# Sheet_1_2023-03-25.net
KiCad netlist of a schematic drawn in Altium Designer
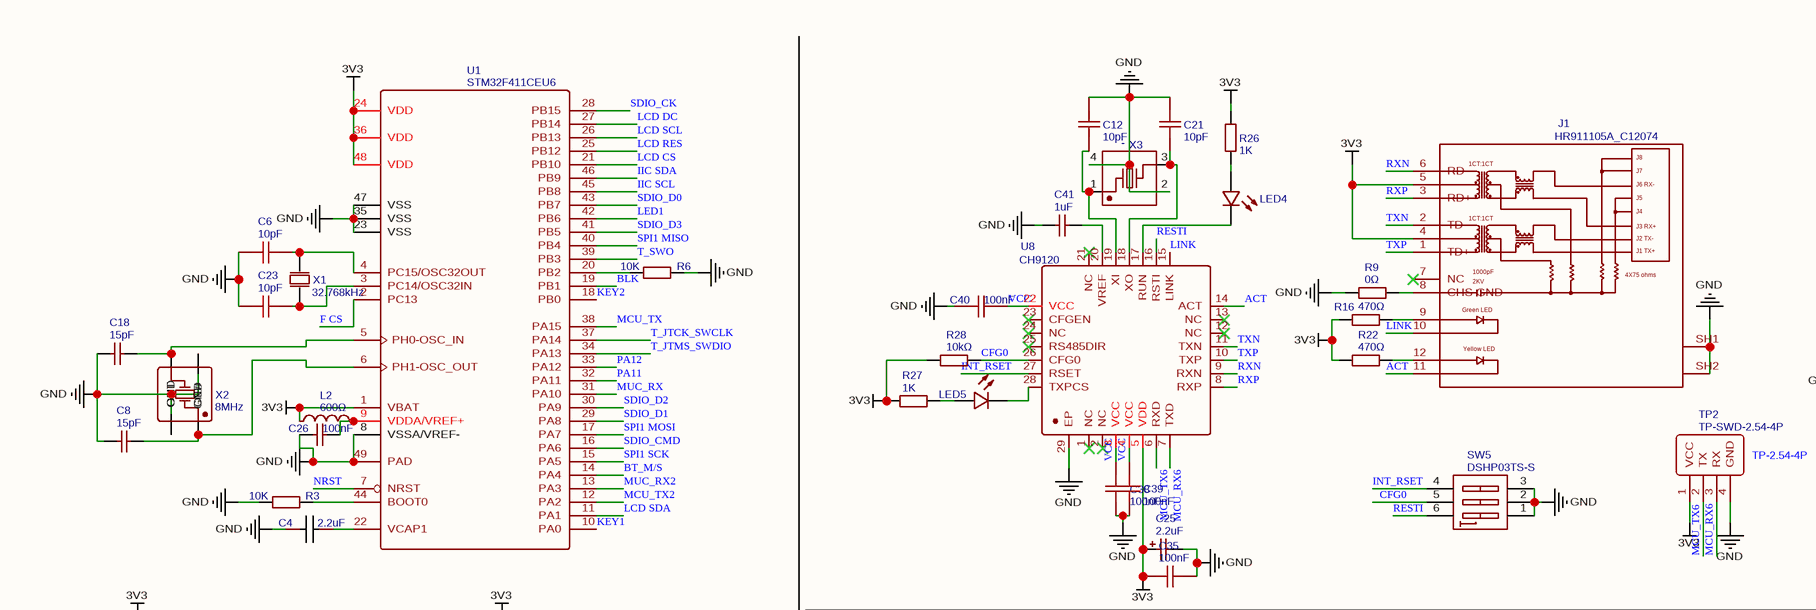
[diagram p0: Sheet_1_2023-03-25.schdoc, top left]
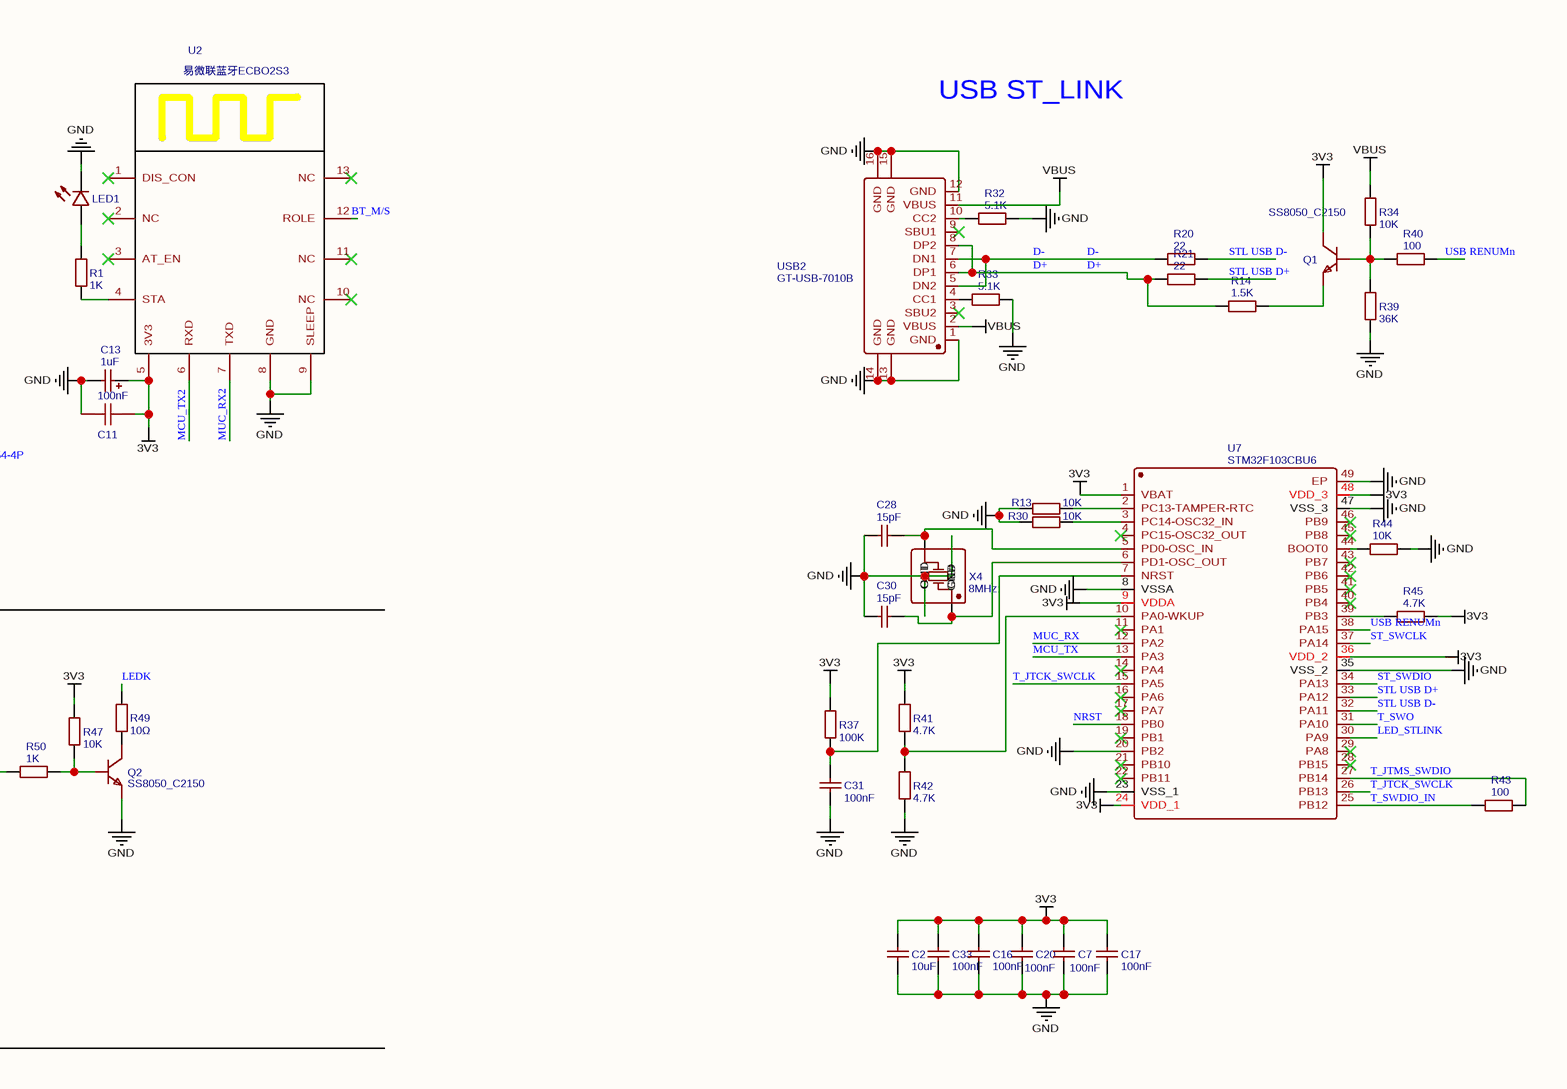
[diagram p1: Sheet_1_2023-03-25.schdoc, top middle]
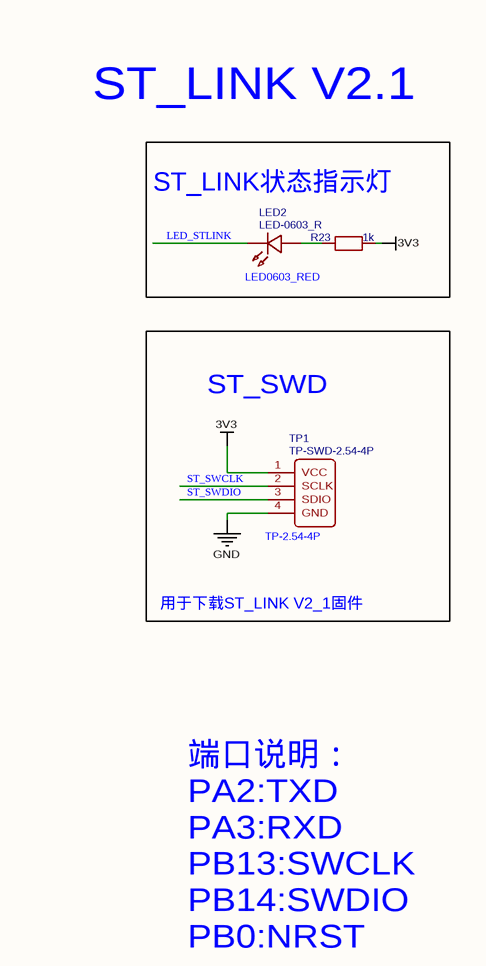
[diagram p2: Sheet_1_2023-03-25.schdoc, top right]
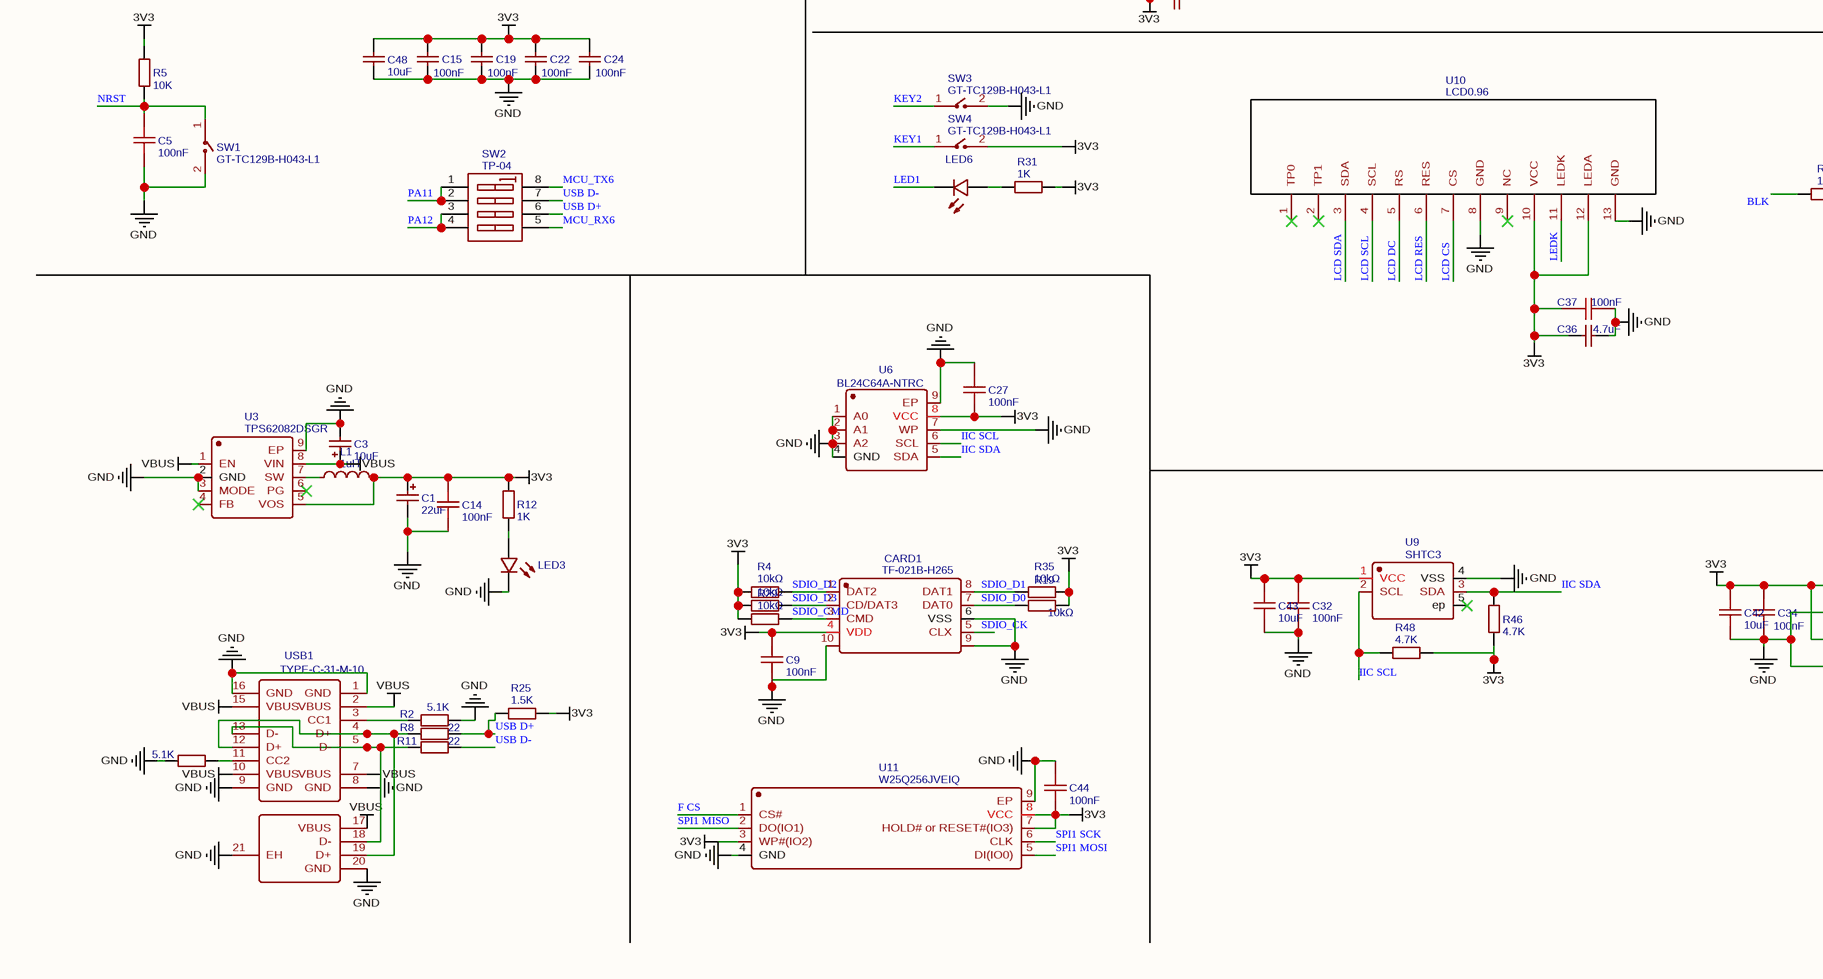
[diagram p3: Sheet_1_2023-03-25.schdoc, bottom left]
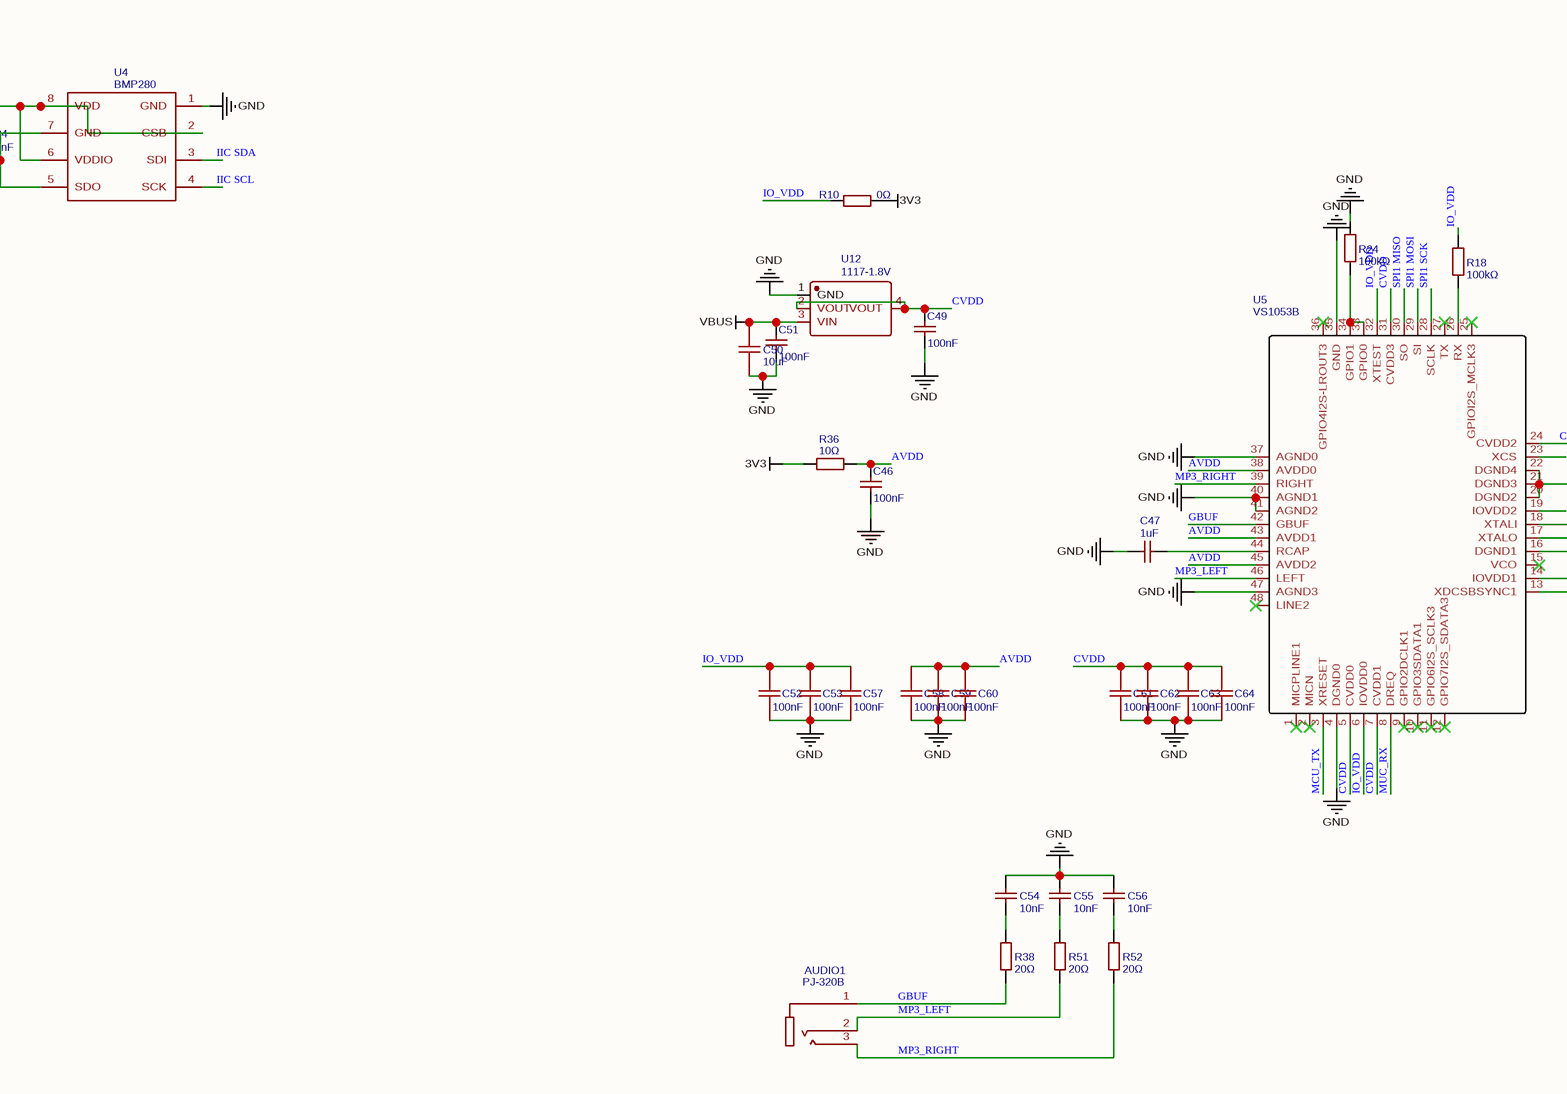
[diagram p4: Sheet_1_2023-03-25.schdoc, bottom middle]
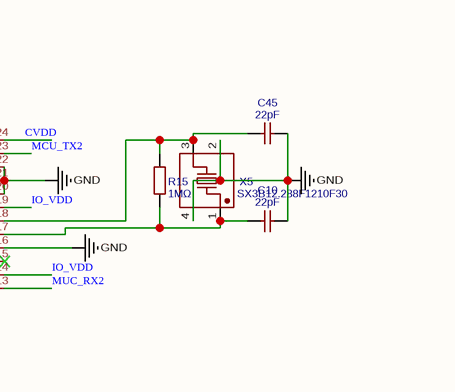
[diagram p5: Sheet_1_2023-03-25.schdoc, bottom right]

(export (version "E")
  (design (tool "Eeschema 10.0.6"))
  (components
    (comp (ref "AUDIO1")
      (value "PJ-320B")
      (fields (field (name "BOM_SUPPLIER PART") "C18594") (field (name "CONTRIBUTOR") "LCSC"))
      (libsource (lib "altium-import") (part "root_0_PJ-320B_"))
    )
    (comp (ref "C1")
      (value "22uF")
      (fields
        (field (name "BOM_MANUFACTURER PART") "TC212A226M010A")
        (field (name "BOM_SUPPLIER PART") "C97062")
      )
      (libsource (lib "altium-import") (part "root_1_22uF_"))
    )
    (comp (ref "C2")
      (value "10uF")
      (fields
        (field (name "BOM_MANUFACTURER PART") "CL05A106MQ5NUNC")
        (field (name "BOM_SUPPLIER PART") "C15525")
      )
      (libsource (lib "altium-import") (part "root_1_10uF_"))
    )
    (comp (ref "C3")
      (value "10uF")
      (fields
        (field (name "BOM_MANUFACTURER PART") "TC212A106K016B")
        (field (name "BOM_SUPPLIER PART") "C124854")
      )
      (libsource (lib "altium-import") (part "root_3_10uF_"))
    )
    (comp (ref "C4")
      (value "2.2uF")
      (fields
        (field (name "BOM_MANUFACTURER PART") "CL05A225MQ5NSNC")
        (field (name "BOM_SUPPLIER PART") "C12530")
      )
      (libsource (lib "altium-import") (part "root_0_2.2uF_"))
    )
    (comp (ref "C5")
      (value "100nF")
      (fields
        (field (name "BOM_MANUFACTURER PART") "CC0603KRX7R9BB104")
        (field (name "BOM_SUPPLIER PART") "C14663")
      )
      (libsource (lib "") (part "root_1_100nF__1"))
    )
    (comp (ref "C6")
      (value "10pF")
      (fields
        (field (name "BOM_MANUFACTURER PART") "CL05C100JB5NNNC")
        (field (name "BOM_SUPPLIER PART") "C32949")
      )
      (libsource (lib "altium-import") (part "root_2_10pF_"))
    )
    (comp (ref "C7")
      (value "100nF")
      (fields
        (field (name "BOM_MANUFACTURER PART") "CL05B104KO5NNNC")
        (field (name "BOM_SUPPLIER PART") "C1525")
      )
      (libsource (lib "altium-import") (part "root_1_100nF_"))
    )
    (comp (ref "C8")
      (value "15pF")
      (fields
        (field (name "BOM_MANUFACTURER PART") "0402CG150J500NT")
        (field (name "BOM_SUPPLIER PART") "C1548")
      )
      (libsource (lib "altium-import") (part "root_0_15pF_"))
    )
    (comp (ref "C9")
      (value "100nF")
      (fields
        (field (name "BOM_MANUFACTURER PART") "CC0603KRX7R9BB104")
        (field (name "BOM_SUPPLIER PART") "C14663")
      )
      (libsource (lib "") (part "root_1_100nF__1"))
    )
    (comp (ref "C10")
      (value "22pF")
      (fields
        (field (name "BOM_MANUFACTURER PART") "CL10C220JB8NNNC")
        (field (name "BOM_SUPPLIER PART") "C1653")
      )
      (libsource (lib "altium-import") (part "root_2_22pF_"))
    )
    (comp (ref "C11")
      (value "100nF")
      (fields
        (field (name "BOM_MANUFACTURER PART") "CC0603KRX7R9BB104")
        (field (name "BOM_SUPPLIER PART") "C14663")
      )
      (libsource (lib "altium-import") (part "root_2_100nF_"))
    )
    (comp (ref "C12")
      (value "10pF")
      (fields
        (field (name "BOM_MANUFACTURER PART") "CL05C100JB5NNNC")
        (field (name "BOM_SUPPLIER PART") "C32949")
      )
      (libsource (lib "altium-import") (part "root_3_10pF_"))
    )
    (comp (ref "C13")
      (value "1uF")
      (fields
        (field (name "BOM_MANUFACTURER PART") "TAJA105K016RNJ")
        (field (name "BOM_SUPPLIER PART") "C7174")
      )
      (libsource (lib "altium-import") (part "root_2_1uF_"))
    )
    (comp (ref "C14")
      (value "100nF")
      (fields
        (field (name "BOM_MANUFACTURER PART") "CC0603KRX7R9BB104")
        (field (name "BOM_SUPPLIER PART") "C14663")
      )
      (libsource (lib "") (part "root_1_100nF__1"))
    )
    (comp (ref "C15")
      (value "100nF")
      (fields
        (field (name "BOM_MANUFACTURER PART") "CL05B104KO5NNNC")
        (field (name "BOM_SUPPLIER PART") "C1525")
      )
      (libsource (lib "altium-import") (part "root_1_100nF_"))
    )
    (comp (ref "C16")
      (value "100nF")
      (fields
        (field (name "BOM_MANUFACTURER PART") "CL05B104KO5NNNC")
        (field (name "BOM_SUPPLIER PART") "C1525")
      )
      (libsource (lib "altium-import") (part "root_1_100nF_"))
    )
    (comp (ref "C17")
      (value "100nF")
      (fields
        (field (name "BOM_MANUFACTURER PART") "CL05B104KO5NNNC")
        (field (name "BOM_SUPPLIER PART") "C1525")
      )
      (libsource (lib "altium-import") (part "root_1_100nF_"))
    )
    (comp (ref "C18")
      (value "15pF")
      (fields
        (field (name "BOM_MANUFACTURER PART") "0402CG150J500NT")
        (field (name "BOM_SUPPLIER PART") "C1548")
      )
      (libsource (lib "altium-import") (part "root_0_15pF_"))
    )
    (comp (ref "C19")
      (value "100nF")
      (fields
        (field (name "BOM_MANUFACTURER PART") "CL05B104KO5NNNC")
        (field (name "BOM_SUPPLIER PART") "C1525")
      )
      (libsource (lib "altium-import") (part "root_1_100nF_"))
    )
    (comp (ref "C20")
      (value "100nF")
      (fields
        (field (name "BOM_MANUFACTURER PART") "CL05B104KO5NNNC")
        (field (name "BOM_SUPPLIER PART") "C1525")
      )
      (libsource (lib "altium-import") (part "root_1_100nF_"))
    )
    (comp (ref "C21")
      (value "10pF")
      (fields
        (field (name "BOM_MANUFACTURER PART") "CL05C100JB5NNNC")
        (field (name "BOM_SUPPLIER PART") "C32949")
      )
      (libsource (lib "altium-import") (part "root_3_10pF_"))
    )
    (comp (ref "C22")
      (value "100nF")
      (fields
        (field (name "BOM_MANUFACTURER PART") "CL05B104KO5NNNC")
        (field (name "BOM_SUPPLIER PART") "C1525")
      )
      (libsource (lib "altium-import") (part "root_1_100nF_"))
    )
    (comp (ref "C23")
      (value "10pF")
      (fields
        (field (name "BOM_MANUFACTURER PART") "CL05C100JB5NNNC")
        (field (name "BOM_SUPPLIER PART") "C32949")
      )
      (libsource (lib "altium-import") (part "root_2_10pF_"))
    )
    (comp (ref "C24")
      (value "100nF")
      (fields
        (field (name "BOM_MANUFACTURER PART") "CL05B104KO5NNNC")
        (field (name "BOM_SUPPLIER PART") "C1525")
      )
      (libsource (lib "altium-import") (part "root_1_100nF_"))
    )
    (comp (ref "C25")
      (value "2.2uF")
      (fields
        (field (name "BOM_MANUFACTURER PART") "TAJA225K016RNJ")
        (field (name "BOM_SUPPLIER PART") "C7180")
      )
      (libsource (lib "") (part "root_0_2.2uF__1"))
    )
    (comp (ref "C26")
      (value "100nF")
      (fields
        (field (name "BOM_MANUFACTURER PART") "CL05B104KO5NNNC")
        (field (name "BOM_SUPPLIER PART") "C1525")
      )
      (libsource (lib "") (part "root_2_100nF__1"))
    )
    (comp (ref "C27")
      (value "100nF")
      (fields
        (field (name "BOM_MANUFACTURER PART") "CC0603KRX7R9BB104")
        (field (name "BOM_SUPPLIER PART") "C14663")
      )
      (libsource (lib "") (part "root_1_100nF__1"))
    )
    (comp (ref "C28")
      (value "15pF")
      (fields
        (field (name "BOM_MANUFACTURER PART") "0402CG150J500NT")
        (field (name "BOM_SUPPLIER PART") "C1548")
      )
      (libsource (lib "altium-import") (part "root_0_15pF_"))
    )
    (comp (ref "C30")
      (value "15pF")
      (fields
        (field (name "BOM_MANUFACTURER PART") "0402CG150J500NT")
        (field (name "BOM_SUPPLIER PART") "C1548")
      )
      (libsource (lib "altium-import") (part "root_0_15pF_"))
    )
    (comp (ref "C31")
      (value "100nF")
      (fields
        (field (name "BOM_MANUFACTURER PART") "CL05B104KO5NNNC")
        (field (name "BOM_SUPPLIER PART") "C1525")
      )
      (libsource (lib "altium-import") (part "root_1_100nF_"))
    )
    (comp (ref "C32")
      (value "100nF")
      (fields
        (field (name "BOM_MANUFACTURER PART") "CC0603KRX7R9BB104")
        (field (name "BOM_SUPPLIER PART") "C14663")
      )
      (libsource (lib "") (part "root_1_100nF__1"))
    )
    (comp (ref "C33")
      (value "100nF")
      (fields
        (field (name "BOM_MANUFACTURER PART") "CL05B104KO5NNNC")
        (field (name "BOM_SUPPLIER PART") "C1525")
      )
      (libsource (lib "altium-import") (part "root_1_100nF_"))
    )
    (comp (ref "C34")
      (value "100nF")
      (fields
        (field (name "BOM_MANUFACTURER PART") "CC0603KRX7R9BB104")
        (field (name "BOM_SUPPLIER PART") "C14663")
      )
      (libsource (lib "") (part "root_1_100nF__1"))
    )
    (comp (ref "C35")
      (value "100nF")
      (fields
        (field (name "BOM_MANUFACTURER PART") "CC0603KRX7R9BB104")
        (field (name "BOM_SUPPLIER PART") "C14663")
      )
      (libsource (lib "altium-import") (part "root_0_100nF_"))
    )
    (comp (ref "C36")
      (value "4.7uF")
      (fields
        (field (name "BOM_MANUFACTURER PART") "CL10A475KO8NNNC")
        (field (name "BOM_SUPPLIER PART") "C19666")
      )
      (libsource (lib "altium-import") (part "root_0_4.7uF_"))
    )
    (comp (ref "C37")
      (value "100nF")
      (fields
        (field (name "BOM_MANUFACTURER PART") "CC0603KRX7R9BB104")
        (field (name "BOM_SUPPLIER PART") "C14663")
      )
      (libsource (lib "altium-import") (part "root_2_100nF_"))
    )
    (comp (ref "C38")
      (value "100nF")
      (fields
        (field (name "BOM_MANUFACTURER PART") "CC0603KRX7R9BB104")
        (field (name "BOM_SUPPLIER PART") "C14663")
      )
      (libsource (lib "altium-import") (part "root_3_100nF_"))
    )
    (comp (ref "C39")
      (value "100nF")
      (fields
        (field (name "BOM_MANUFACTURER PART") "CC0603KRX7R9BB104")
        (field (name "BOM_SUPPLIER PART") "C14663")
      )
      (libsource (lib "altium-import") (part "root_3_100nF_"))
    )
    (comp (ref "C40")
      (value "100nF")
      (fields
        (field (name "BOM_MANUFACTURER PART") "CC0603KRX7R9BB104")
        (field (name "BOM_SUPPLIER PART") "C14663")
      )
      (libsource (lib "altium-import") (part "root_2_100nF_"))
    )
    (comp (ref "C41")
      (value "1uF")
      (fields
        (field (name "BOM_MANUFACTURER PART") "CL10A105KB8NNNC")
        (field (name "BOM_SUPPLIER PART") "C15849")
      )
      (libsource (lib "altium-import") (part "root_0_1uF_"))
    )
    (comp (ref "C42")
      (value "10uF")
      (fields
        (field (name "BOM_MANUFACTURER PART") "CL10A106KP8NNNC")
        (field (name "BOM_SUPPLIER PART") "C19702")
      )
      (libsource (lib "") (part "root_1_10uF__1"))
    )
    (comp (ref "C43")
      (value "10uF")
      (fields
        (field (name "BOM_MANUFACTURER PART") "CL10A106KP8NNNC")
        (field (name "BOM_SUPPLIER PART") "C19702")
      )
      (libsource (lib "") (part "root_1_10uF__1"))
    )
    (comp (ref "C44")
      (value "100nF")
      (fields
        (field (name "BOM_MANUFACTURER PART") "CC0603KRX7R9BB104")
        (field (name "BOM_SUPPLIER PART") "C14663")
      )
      (libsource (lib "altium-import") (part "root_3_100nF_"))
    )
    (comp (ref "C45")
      (value "22pF")
      (fields
        (field (name "BOM_MANUFACTURER PART") "CL10C220JB8NNNC")
        (field (name "BOM_SUPPLIER PART") "C1653")
      )
      (libsource (lib "altium-import") (part "root_2_22pF_"))
    )
    (comp (ref "C46")
      (value "100nF")
      (fields
        (field (name "BOM_MANUFACTURER PART") "CC0603KRX7R8BB104")
        (field (name "BOM_SUPPLIER PART") "C92490")
      )
      (libsource (lib "altium-import") (part "root_1_100nF_"))
    )
    (comp (ref "C47")
      (value "1uF")
      (fields
        (field (name "BOM_MANUFACTURER PART") "CL10A105KB8NNNC")
        (field (name "BOM_SUPPLIER PART") "C15849")
      )
      (libsource (lib "altium-import") (part "root_0_1uF_"))
    )
    (comp (ref "C48")
      (value "10uF")
      (fields
        (field (name "BOM_MANUFACTURER PART") "CL05A106MQ5NUNC")
        (field (name "BOM_SUPPLIER PART") "C15525")
      )
      (libsource (lib "altium-import") (part "root_1_10uF_"))
    )
    (comp (ref "C49")
      (value "100nF")
      (fields
        (field (name "BOM_MANUFACTURER PART") "CC0603KRX7R8BB104")
        (field (name "BOM_SUPPLIER PART") "C92490")
      )
      (libsource (lib "altium-import") (part "root_1_100nF_"))
    )
    (comp (ref "C50")
      (value "10uF")
      (fields
        (field (name "BOM_MANUFACTURER PART") "CL10A106KP8NNNC")
        (field (name "BOM_SUPPLIER PART") "C19702")
      )
      (libsource (lib "") (part "root_1_10uF__1"))
    )
    (comp (ref "C51")
      (value "100nF")
      (fields
        (field (name "BOM_MANUFACTURER PART") "CC0603KRX7R8BB104")
        (field (name "BOM_SUPPLIER PART") "C92490")
      )
      (libsource (lib "altium-import") (part "root_1_100nF_"))
    )
    (comp (ref "C52")
      (value "100nF")
      (fields
        (field (name "BOM_MANUFACTURER PART") "CC0603KRX7R9BB104")
        (field (name "BOM_SUPPLIER PART") "C14663")
      )
      (libsource (lib "") (part "root_1_100nF__1"))
    )
    (comp (ref "C53")
      (value "100nF")
      (fields
        (field (name "BOM_MANUFACTURER PART") "CC0603KRX7R9BB104")
        (field (name "BOM_SUPPLIER PART") "C14663")
      )
      (libsource (lib "") (part "root_1_100nF__1"))
    )
    (comp (ref "C54")
      (value "10nF")
      (fields
        (field (name "BOM_MANUFACTURER PART") "0603B103K500NT")
        (field (name "BOM_SUPPLIER PART") "C57112")
      )
      (libsource (lib "altium-import") (part "root_1_10nF_"))
    )
    (comp (ref "C55")
      (value "10nF")
      (fields
        (field (name "BOM_MANUFACTURER PART") "0603B103K500NT")
        (field (name "BOM_SUPPLIER PART") "C57112")
      )
      (libsource (lib "altium-import") (part "root_1_10nF_"))
    )
    (comp (ref "C56")
      (value "10nF")
      (fields
        (field (name "BOM_MANUFACTURER PART") "0603B103K500NT")
        (field (name "BOM_SUPPLIER PART") "C57112")
      )
      (libsource (lib "altium-import") (part "root_1_10nF_"))
    )
    (comp (ref "C57")
      (value "100nF")
      (fields
        (field (name "BOM_MANUFACTURER PART") "CC0603KRX7R9BB104")
        (field (name "BOM_SUPPLIER PART") "C14663")
      )
      (libsource (lib "") (part "root_1_100nF__1"))
    )
    (comp (ref "C58")
      (value "100nF")
      (fields
        (field (name "BOM_MANUFACTURER PART") "CC0603KRX7R9BB104")
        (field (name "BOM_SUPPLIER PART") "C14663")
      )
      (libsource (lib "") (part "root_1_100nF__1"))
    )
    (comp (ref "C59")
      (value "100nF")
      (fields
        (field (name "BOM_MANUFACTURER PART") "CC0603KRX7R9BB104")
        (field (name "BOM_SUPPLIER PART") "C14663")
      )
      (libsource (lib "") (part "root_1_100nF__1"))
    )
    (comp (ref "C60")
      (value "100nF")
      (fields
        (field (name "BOM_MANUFACTURER PART") "CC0603KRX7R9BB104")
        (field (name "BOM_SUPPLIER PART") "C14663")
      )
      (libsource (lib "") (part "root_1_100nF__1"))
    )
    (comp (ref "C61")
      (value "100nF")
      (fields
        (field (name "BOM_MANUFACTURER PART") "CC0603KRX7R9BB104")
        (field (name "BOM_SUPPLIER PART") "C14663")
      )
      (libsource (lib "") (part "root_1_100nF__1"))
    )
    (comp (ref "C62")
      (value "100nF")
      (fields
        (field (name "BOM_MANUFACTURER PART") "CC0603KRX7R9BB104")
        (field (name "BOM_SUPPLIER PART") "C14663")
      )
      (libsource (lib "") (part "root_1_100nF__1"))
    )
    (comp (ref "C63")
      (value "100nF")
      (fields
        (field (name "BOM_MANUFACTURER PART") "CC0603KRX7R9BB104")
        (field (name "BOM_SUPPLIER PART") "C14663")
      )
      (libsource (lib "") (part "root_1_100nF__1"))
    )
    (comp (ref "C64")
      (value "100nF")
      (fields
        (field (name "BOM_MANUFACTURER PART") "CC0603KRX7R9BB104")
        (field (name "BOM_SUPPLIER PART") "C14663")
      )
      (libsource (lib "") (part "root_1_100nF__1"))
    )
    (comp (ref "CARD1")
      (value "TF-021B-H265")
      (fields (field (name "BOM_SUPPLIER PART") "C498185") (field (name "CONTRIBUTOR") "LCSC"))
      (libsource (lib "altium-import") (part "root_0_TF-021B-H265_"))
    )
    (comp (ref "J1")
      (value "HR911105A_C12074")
      (fields (field (name "BOM_MANUFACTURER PART") "HR911105A") (field (name "BOM_SUPPLIER PART") "C12074"))
      (libsource (lib "altium-import") (part "root_0_HR911105A_C12074_"))
    )
    (comp (ref "L1")
      (value "1uH")
      (fields
        (field (name "BOM_SUPPLIER PART") "C98388")
        (field (name "BOM_MANUFACTURER PART") "SPH3012H1R0MT")
        (field (name "CONTRIBUTOR") "LCSC")
      )
      (libsource (lib "altium-import") (part "root_0_1uH_"))
    )
    (comp (ref "L2")
      (value "600Ω")
      (fields
        (field (name "BOM_MANUFACTURER PART") "MMZ1005Y601CT000")
        (field (name "BOM_SUPPLIER PART") "C87552")
      )
      (libsource (lib "altium-import") (part "root_0_600Ω_"))
    )
    (comp (ref "LED1")
      (value "19-213/Y2C-CQ2R2L/3T(CY)")
      (fields (field (name "BOM_SUPPLIER PART") "C72038"))
      (libsource (lib "altium-import") (part "root_1_19-213/Y2C-CQ2R2L/3T(CY)_"))
    )
    (comp (ref "LED2")
      (value "LED-0603_R")
      (fields
        (field (name "BOM_MANUFACTURER PART") "19-217/R6C-AL1M2VY/3T")
        (field (name "BOM_SUPPLIER PART") "C72044")
        (field (name "CONTRIBUTOR") "LCEDA_01")
      )
      (libsource (lib "altium-import") (part "root_2_LED-0603_R_"))
    )
    (comp (ref "LED3")
      (value "19-213/Y2C-CQ2R2L/3T(CY)")
      (fields (field (name "BOM_SUPPLIER PART") "C72038"))
      (libsource (lib "altium-import") (part "root_3_19-213/Y2C-CQ2R2L/3T(CY)_"))
    )
    (comp (ref "LED4")
      (value "19-213/Y2C-CQ2R2L/3T(CY)")
      (fields (field (name "BOM_SUPPLIER PART") "C72038"))
      (libsource (lib "altium-import") (part "root_3_19-213/Y2C-CQ2R2L/3T(CY)_"))
    )
    (comp (ref "LED5")
      (value "19-213/Y2C-CQ2R2L/3T(CY)")
      (fields (field (name "BOM_SUPPLIER PART") "C72038"))
      (libsource (lib "altium-import") (part "root_0_19-213/Y2C-CQ2R2L/3T(CY)_"))
    )
    (comp (ref "LED6")
      (value "19-213/Y2C-CQ2R2L/3T(CY)")
      (fields (field (name "BOM_SUPPLIER PART") "C72038"))
      (libsource (lib "altium-import") (part "root_2_19-213/Y2C-CQ2R2L/3T(CY)_"))
    )
    (comp (ref "Q1")
      (value "SS8050_C2150")
      (fields (field (name "BOM_MANUFACTURER PART") "SS8050") (field (name "BOM_SUPPLIER PART") "C2150"))
      (libsource (lib "altium-import") (part "root_0_SS8050_C2150_"))
    )
    (comp (ref "Q2")
      (value "SS8050_C2150")
      (fields (field (name "BOM_MANUFACTURER PART") "SS8050") (field (name "BOM_SUPPLIER PART") "C2150"))
      (libsource (lib "") (part "root_0_SS8050_C2150__1"))
    )
    (comp (ref "R1")
      (value "1K")
      (fields
        (field (name "BOM_MANUFACTURER PART") "0603WAF1001T5E")
        (field (name "BOM_SUPPLIER PART") "C21190")
      )
      (libsource (lib "altium-import") (part "root_3_1K_"))
    )
    (comp (ref "R2")
      (value "5.1K")
      (fields
        (field (name "BOM_MANUFACTURER PART") "0603WAF5101T5E")
        (field (name "BOM_SUPPLIER PART") "C23186")
      )
      (libsource (lib "altium-import") (part "root_0_5.1K_"))
    )
    (comp (ref "R3")
      (value "10K")
      (fields
        (field (name "BOM_MANUFACTURER PART") "0402WGF1002TCE")
        (field (name "BOM_SUPPLIER PART") "C25744")
      )
      (libsource (lib "altium-import") (part "root_0_10K_"))
    )
    (comp (ref "R4")
      (value "10kΩ")
      (fields
        (field (name "BOM_MANUFACTURER PART") "0603WAF1002T5E")
        (field (name "BOM_SUPPLIER PART") "C25804")
      )
      (libsource (lib "altium-import") (part "root_0_10kΩ_"))
    )
    (comp (ref "R5")
      (value "10K")
      (fields
        (field (name "BOM_SUPPLIER PART") "C319937")
        (field (name "BOM_MANUFACTURER PART") "AR03DTCX1002")
        (field (name "CONTRIBUTOR") "LCSC")
      )
      (libsource (lib "altium-import") (part "root_3_10K_"))
    )
    (comp (ref "R6")
      (value "10K")
      (fields
        (field (name "BOM_MANUFACTURER PART") "0402WGF1002TCE")
        (field (name "BOM_SUPPLIER PART") "C25744")
      )
      (libsource (lib "altium-import") (part "root_0_10K_"))
    )
    (comp (ref "R7")
      (value "5.1K")
      (fields
        (field (name "BOM_MANUFACTURER PART") "0603WAF5101T5E")
        (field (name "BOM_SUPPLIER PART") "C23186")
      )
      (libsource (lib "altium-import") (part "root_0_5.1K_"))
    )
    (comp (ref "R8")
      (value "22")
      (fields
        (field (name "BOM_MANUFACTURER PART") "0603WAF220JT5E")
        (field (name "BOM_SUPPLIER PART") "C23345")
      )
      (libsource (lib "altium-import") (part "root_0_22_"))
    )
    (comp (ref "R9")
      (value "0Ω")
      (fields
        (field (name "BOM_MANUFACTURER PART") "0603WAF0000T5E")
        (field (name "BOM_SUPPLIER PART") "C21189")
      )
      (libsource (lib "altium-import") (part "root_0_0Ω_"))
    )
    (comp (ref "R10")
      (value "0Ω")
      (fields
        (field (name "BOM_MANUFACTURER PART") "0603WAF0000T5E")
        (field (name "BOM_SUPPLIER PART") "C21189")
      )
      (libsource (lib "altium-import") (part "root_0_0Ω_"))
    )
    (comp (ref "R11")
      (value "22")
      (fields
        (field (name "BOM_MANUFACTURER PART") "0603WAF220JT5E")
        (field (name "BOM_SUPPLIER PART") "C23345")
      )
      (libsource (lib "altium-import") (part "root_0_22_"))
    )
    (comp (ref "R12")
      (value "1K")
      (fields
        (field (name "BOM_MANUFACTURER PART") "0603WAF1001T5E")
        (field (name "BOM_SUPPLIER PART") "C21190")
      )
      (libsource (lib "altium-import") (part "root_1_1K_"))
    )
    (comp (ref "R13")
      (value "10K")
      (fields
        (field (name "BOM_MANUFACTURER PART") "0402WGF1002TCE")
        (field (name "BOM_SUPPLIER PART") "C25744")
      )
      (libsource (lib "altium-import") (part "root_2_10K_"))
    )
    (comp (ref "R14")
      (value "1.5K")
      (fields
        (field (name "BOM_MANUFACTURER PART") "0603WAF1501T5E")
        (field (name "BOM_SUPPLIER PART") "C22843")
      )
      (libsource (lib "altium-import") (part "root_2_1.5K_"))
    )
    (comp (ref "R15")
      (value "1MΩ")
      (fields
        (field (name "BOM_MANUFACTURER PART") "0603WAF1004T5E")
        (field (name "BOM_SUPPLIER PART") "C22935")
      )
      (libsource (lib "altium-import") (part "root_3_1MΩ_"))
    )
    (comp (ref "R16")
      (value "470Ω")
      (fields
        (field (name "BOM_MANUFACTURER PART") "0603WAF4700T5E")
        (field (name "BOM_SUPPLIER PART") "C23179")
      )
      (libsource (lib "altium-import") (part "root_0_470Ω_"))
    )
    (comp (ref "R17")
      (value "10kΩ")
      (fields
        (field (name "BOM_MANUFACTURER PART") "0603WAF1002T5E")
        (field (name "BOM_SUPPLIER PART") "C25804")
      )
      (libsource (lib "altium-import") (part "root_0_10kΩ_"))
    )
    (comp (ref "R18")
      (value "100kΩ")
      (fields
        (field (name "BOM_MANUFACTURER PART") "0603WAF1003T5E")
        (field (name "BOM_SUPPLIER PART") "C25803")
      )
      (libsource (lib "altium-import") (part "root_1_100kΩ_"))
    )
    (comp (ref "R19")
      (value "10kΩ")
      (fields
        (field (name "BOM_MANUFACTURER PART") "0603WAF1002T5E")
        (field (name "BOM_SUPPLIER PART") "C25804")
      )
      (libsource (lib "altium-import") (part "root_0_10kΩ_"))
    )
    (comp (ref "R20")
      (value "22")
      (fields
        (field (name "BOM_MANUFACTURER PART") "0603WAF220JT5E")
        (field (name "BOM_SUPPLIER PART") "C23345")
      )
      (libsource (lib "altium-import") (part "root_0_22_"))
    )
    (comp (ref "R21")
      (value "22")
      (fields
        (field (name "BOM_MANUFACTURER PART") "0603WAF220JT5E")
        (field (name "BOM_SUPPLIER PART") "C23345")
      )
      (libsource (lib "altium-import") (part "root_0_22_"))
    )
    (comp (ref "R22")
      (value "470Ω")
      (fields
        (field (name "BOM_MANUFACTURER PART") "0603WAF4700T5E")
        (field (name "BOM_SUPPLIER PART") "C23179")
      )
      (libsource (lib "altium-import") (part "root_0_470Ω_"))
    )
    (comp (ref "R23")
      (value "1k")
      (fields (field (name "BOM_SUPPLIER PART") "C22548"))
      (libsource (lib "altium-import") (part "root_2_1k_"))
    )
    (comp (ref "R24")
      (value "100kΩ")
      (fields
        (field (name "BOM_MANUFACTURER PART") "0603WAF1003T5E")
        (field (name "BOM_SUPPLIER PART") "C25803")
      )
      (libsource (lib "altium-import") (part "root_1_100kΩ_"))
    )
    (comp (ref "R25")
      (value "1.5K")
      (fields
        (field (name "BOM_MANUFACTURER PART") "0603WAF1501T5E")
        (field (name "BOM_SUPPLIER PART") "C22843")
      )
      (libsource (lib "altium-import") (part "root_0_1.5K_"))
    )
    (comp (ref "R26")
      (value "1K")
      (fields
        (field (name "BOM_MANUFACTURER PART") "0603WAF1001T5E")
        (field (name "BOM_SUPPLIER PART") "C21190")
      )
      (libsource (lib "altium-import") (part "root_1_1K_"))
    )
    (comp (ref "R27")
      (value "1K")
      (fields
        (field (name "BOM_MANUFACTURER PART") "0603WAF1001T5E")
        (field (name "BOM_SUPPLIER PART") "C21190")
      )
      (libsource (lib "altium-import") (part "root_2_1K_"))
    )
    (comp (ref "R28")
      (value "10kΩ")
      (fields
        (field (name "BOM_MANUFACTURER PART") "0603WAF1002T5E")
        (field (name "BOM_SUPPLIER PART") "C25804")
      )
      (libsource (lib "altium-import") (part "root_0_10kΩ_"))
    )
    (comp (ref "R29")
      (value "10kΩ")
      (fields
        (field (name "BOM_MANUFACTURER PART") "0603WAF1002T5E")
        (field (name "BOM_SUPPLIER PART") "C25804")
      )
      (libsource (lib "altium-import") (part "root_0_10kΩ_"))
    )
    (comp (ref "R30")
      (value "10K")
      (fields
        (field (name "BOM_MANUFACTURER PART") "0402WGF1002TCE")
        (field (name "BOM_SUPPLIER PART") "C25744")
      )
      (libsource (lib "altium-import") (part "root_2_10K_"))
    )
    (comp (ref "R31")
      (value "1K")
      (fields
        (field (name "BOM_MANUFACTURER PART") "0603WAF1001T5E")
        (field (name "BOM_SUPPLIER PART") "C21190")
      )
      (libsource (lib "altium-import") (part "root_0_1K_"))
    )
    (comp (ref "R32")
      (value "5.1K")
      (fields
        (field (name "BOM_MANUFACTURER PART") "0603WAF5101T5E")
        (field (name "BOM_SUPPLIER PART") "C23186")
      )
      (libsource (lib "altium-import") (part "root_0_5.1K_"))
    )
    (comp (ref "R33")
      (value "5.1K")
      (fields
        (field (name "BOM_MANUFACTURER PART") "0603WAF5101T5E")
        (field (name "BOM_SUPPLIER PART") "C23186")
      )
      (libsource (lib "altium-import") (part "root_0_5.1K_"))
    )
    (comp (ref "R34")
      (value "10K")
      (fields
        (field (name "BOM_SUPPLIER PART") "C319937")
        (field (name "BOM_MANUFACTURER PART") "AR03DTCX1002")
        (field (name "CONTRIBUTOR") "LCSC")
      )
      (libsource (lib "altium-import") (part "root_1_10K_"))
    )
    (comp (ref "R35")
      (value "10kΩ")
      (fields
        (field (name "BOM_MANUFACTURER PART") "0603WAF1002T5E")
        (field (name "BOM_SUPPLIER PART") "C25804")
      )
      (libsource (lib "altium-import") (part "root_0_10kΩ_"))
    )
    (comp (ref "R36")
      (value "10Ω")
      (fields
        (field (name "BOM_MANUFACTURER PART") "0603WAF100JT5E")
        (field (name "BOM_SUPPLIER PART") "C22859")
      )
      (libsource (lib "altium-import") (part "root_2_10Ω_"))
    )
    (comp (ref "R37")
      (value "100K")
      (fields
        (field (name "BOM_MANUFACTURER PART") "0402WGF1003TCE")
        (field (name "BOM_SUPPLIER PART") "C25741")
      )
      (libsource (lib "altium-import") (part "root_1_100K_"))
    )
    (comp (ref "R38")
      (value "20Ω")
      (fields
        (field (name "BOM_MANUFACTURER PART") "0603WAF200JT5E")
        (field (name "BOM_SUPPLIER PART") "C22950")
      )
      (libsource (lib "altium-import") (part "root_1_20Ω_"))
    )
    (comp (ref "R39")
      (value "36K")
      (fields
        (field (name "BOM_MANUFACTURER PART") "0603WAF3602T5E")
        (field (name "BOM_SUPPLIER PART") "C23147")
      )
      (libsource (lib "altium-import") (part "root_1_36K_"))
    )
    (comp (ref "R40")
      (value "100")
      (fields
        (field (name "BOM_MANUFACTURER PART") "0603WAF1000T5E")
        (field (name "BOM_SUPPLIER PART") "C22775")
      )
      (libsource (lib "altium-import") (part "root_0_100_"))
    )
    (comp (ref "R41")
      (value "4.7K")
      (fields
        (field (name "BOM_MANUFACTURER PART") "0402WGF4701TCE")
        (field (name "BOM_SUPPLIER PART") "C25900")
      )
      (libsource (lib "altium-import") (part "root_3_4.7K_"))
    )
    (comp (ref "R42")
      (value "4.7K")
      (fields
        (field (name "BOM_MANUFACTURER PART") "0402WGF4701TCE")
        (field (name "BOM_SUPPLIER PART") "C25900")
      )
      (libsource (lib "altium-import") (part "root_3_4.7K_"))
    )
    (comp (ref "R43")
      (value "100")
      (fields
        (field (name "BOM_MANUFACTURER PART") "0402WGF1000TCE")
        (field (name "BOM_SUPPLIER PART") "C25076")
      )
      (libsource (lib "altium-import") (part "root_0_100_"))
    )
    (comp (ref "R44")
      (value "10K")
      (fields
        (field (name "BOM_MANUFACTURER PART") "0402WGF1002TCE")
        (field (name "BOM_SUPPLIER PART") "C25744")
      )
      (libsource (lib "altium-import") (part "root_2_10K_"))
    )
    (comp (ref "R45")
      (value "4.7K")
      (fields
        (field (name "BOM_MANUFACTURER PART") "0402WGF4701TCE")
        (field (name "BOM_SUPPLIER PART") "C25900")
      )
      (libsource (lib "altium-import") (part "root_2_4.7K_"))
    )
    (comp (ref "R46")
      (value "4.7K")
      (fields
        (field (name "BOM_MANUFACTURER PART") "0603WAJ0472T5E")
        (field (name "BOM_SUPPLIER PART") "C25999")
      )
      (libsource (lib "altium-import") (part "root_1_4.7K_"))
    )
    (comp (ref "R47")
      (value "10K")
      (fields
        (field (name "BOM_MANUFACTURER PART") "0603WAF1002T5E")
        (field (name "BOM_SUPPLIER PART") "C25804")
      )
      (libsource (lib "altium-import") (part "root_1_10K_"))
    )
    (comp (ref "R48")
      (value "4.7K")
      (fields
        (field (name "BOM_MANUFACTURER PART") "0603WAJ0472T5E")
        (field (name "BOM_SUPPLIER PART") "C25999")
      )
      (libsource (lib "altium-import") (part "root_2_4.7K_"))
    )
    (comp (ref "R49")
      (value "10Ω")
      (fields
        (field (name "BOM_MANUFACTURER PART") "0603WAF100JT5E")
        (field (name "BOM_SUPPLIER PART") "C22859")
      )
      (libsource (lib "altium-import") (part "root_1_10Ω_"))
    )
    (comp (ref "R50")
      (value "1K")
      (fields
        (field (name "BOM_MANUFACTURER PART") "0603WAF1001T5E")
        (field (name "BOM_SUPPLIER PART") "C21190")
      )
      (libsource (lib "") (part "root_0_1K__1"))
    )
    (comp (ref "R51")
      (value "20Ω")
      (fields
        (field (name "BOM_MANUFACTURER PART") "0603WAF200JT5E")
        (field (name "BOM_SUPPLIER PART") "C22950")
      )
      (libsource (lib "altium-import") (part "root_1_20Ω_"))
    )
    (comp (ref "R52")
      (value "20Ω")
      (fields
        (field (name "BOM_MANUFACTURER PART") "0603WAF200JT5E")
        (field (name "BOM_SUPPLIER PART") "C22950")
      )
      (libsource (lib "altium-import") (part "root_1_20Ω_"))
    )
    (comp (ref "SW1")
      (value "GT-TC129B-H043-L1")
      (fields (field (name "BOM_SUPPLIER PART") "C2930980") (field (name "CONTRIBUTOR") "LCSC"))
      (libsource (lib "altium-import") (part "root_3_GT-TC129B-H043-L1_"))
    )
    (comp (ref "SW2")
      (value "TP-04")
      (fields (field (name "BOM_SUPPLIER PART") "C559167") (field (name "CONTRIBUTOR") "LCSC"))
      (libsource (lib "altium-import") (part "root_1_TP-04_"))
    )
    (comp (ref "SW3")
      (value "GT-TC129B-H043-L1")
      (fields (field (name "BOM_SUPPLIER PART") "C2930980") (field (name "CONTRIBUTOR") "LCSC"))
      (libsource (lib "altium-import") (part "root_0_GT-TC129B-H043-L1_"))
    )
    (comp (ref "SW4")
      (value "GT-TC129B-H043-L1")
      (fields (field (name "BOM_SUPPLIER PART") "C2930980") (field (name "CONTRIBUTOR") "LCSC"))
      (libsource (lib "altium-import") (part "root_0_GT-TC129B-H043-L1_"))
    )
    (comp (ref "SW5")
      (value "DSHP03TS-S")
      (fields (field (name "BOM_SUPPLIER PART") "C319051") (field (name "CONTRIBUTOR") "LCSC"))
      (libsource (lib "altium-import") (part "root_2_DSHP03TS-S_"))
    )
    (comp (ref "TP1")
      (value "TP-SWD-2.54-4P")
      (fields (field (name "CONTRIBUTOR") "CYIIOT"))
      (libsource (lib "altium-import") (part "root_0_TP-SWD-2.54-4P_"))
    )
    (comp (ref "TP2")
      (value "TP-SWD-2.54-4P")
      (fields (field (name "CONTRIBUTOR") "CYIIOT"))
      (libsource (lib "altium-import") (part "root_1_TP-SWD-2.54-4P_"))
    )
    (comp (ref "U1")
      (value "STM32F411CEU6")
      (fields (field (name "BOM_SUPPLIER PART") "C60420"))
      (libsource (lib "altium-import") (part "root_0_STM32F411CEU6_"))
    )
    (comp (ref "U2")
      (value "易微联蓝牙ECBO2S3")
      (fields (field (name "CONTRIBUTOR") "WTDW"))
      (libsource (lib "altium-import") (part "root_0_易微联蓝牙ECBO2S3_"))
    )
    (comp (ref "U3")
      (value "TPS62082DSGR")
      (fields (field (name "BOM_SUPPLIER PART") "C485809") (field (name "CONTRIBUTOR") "LCSC"))
      (libsource (lib "altium-import") (part "root_0_TPS62082DSGR_"))
    )
    (comp (ref "U4")
      (value "BMP280")
      (fields (field (name "BOM_SUPPLIER PART") "C83291"))
      (libsource (lib "altium-import") (part "root_0_BMP280_"))
    )
    (comp (ref "U5")
      (value "VS1053B")
      (fields (field (name "BOM_SUPPLIER PART") "C9922"))
      (libsource (lib "altium-import") (part "root_1_VS1053B_"))
    )
    (comp (ref "U6")
      (value "BL24C64A-NTRC")
      (fields (field (name "BOM_SUPPLIER PART") "C691879") (field (name "CONTRIBUTOR") "LCSC"))
      (libsource (lib "altium-import") (part "root_0_BL24C64A-NTRC_"))
    )
    (comp (ref "U7")
      (value "STM32F103CBU6")
      (fields (field (name "BOM_SUPPLIER PART") "C55506") (field (name "SUBPART_NO") "1"))
      (libsource (lib "altium-import") (part "root_0_STM32F103CBU6_"))
    )
    (comp (ref "U8")
      (value "CH9120")
      (fields (field (name "BOM_SUPPLIER PART") "C2681747") (field (name "CONTRIBUTOR") "LCSC"))
      (libsource (lib "altium-import") (part "root_0_CH9120_"))
    )
    (comp (ref "U9")
      (value "SHTC3")
      (fields (field (name "BOM_SUPPLIER PART") "C194656") (field (name "CONTRIBUTOR") "LCSC"))
      (libsource (lib "altium-import") (part "root_0_SHTC3_"))
    )
    (comp (ref "U10")
      (value "LCD0.96")
      (fields (field (name "CONTRIBUTOR") "WTDW"))
      (libsource (lib "altium-import") (part "root_0_LCD0.96_"))
    )
    (comp (ref "U11")
      (value "W25Q256JVEIQ")
      (fields (field (name "BOM_SUPPLIER PART") "C2682312") (field (name "CONTRIBUTOR") "LCSC"))
      (libsource (lib "altium-import") (part "root_0_W25Q256JVEIQ_"))
    )
    (comp (ref "U12")
      (value "1117-1.8V")
      (fields (field (name "BOM_SUPPLIER PART") "C845412") (field (name "CONTRIBUTOR") "LCSC"))
      (libsource (lib "altium-import") (part "root_0_1117-1.8V_"))
    )
    (comp (ref "USB1")
      (value "TYPE-C-31-M-10")
      (fields (field (name "BOM_SUPPLIER PART") "C223904") (field (name "CONTRIBUTOR") "LCSC"))
      (libsource (lib "altium-import") (part "root_0_TYPE-C-31-M-10_"))
    )
    (comp (ref "USB2")
      (value "GT-USB-7010B")
      (fields (field (name "BOM_SUPPLIER PART") "C2837092") (field (name "CONTRIBUTOR") "LCSC"))
      (libsource (lib "altium-import") (part "root_2_GT-USB-7010B_"))
    )
    (comp (ref "X1")
      (value "32.768kHz")
      (fields
        (field (name "BOM_MANUFACTURER PART") "FC-12M32.768KHZ7PF20PPM")
        (field (name "BOM_SUPPLIER PART") "C99009")
      )
      (libsource (lib "altium-import") (part "root_1_32.768kHz_"))
    )
    (comp (ref "X2")
      (value "8MHz")
      (fields
        (field (name "BOM_SUPPLIER PART") "C367183")
        (field (name "BOM_MANUFACTURER PART") "XXDCELNANF-8MHZ")
        (field (name "CONTRIBUTOR") "LCSC")
      )
      (libsource (lib "altium-import") (part "root_1_8MHz_"))
    )
    (comp (ref "X3")
      (value "-")
      (fields
        (field (name "BOM_SUPPLIER PART") "C843260")
        (field (name "BOM_MANUFACTURER PART") "NX2016SA-32MHZ-STD-CZS-5")
        (field (name "CONTRIBUTOR") "LCSC")
      )
      (libsource (lib "altium-import") (part "root_0_-_"))
    )
    (comp (ref "X4")
      (value "8MHz")
      (fields
        (field (name "BOM_SUPPLIER PART") "C367183")
        (field (name "BOM_MANUFACTURER PART") "XXDCELNANF-8MHZ")
        (field (name "CONTRIBUTOR") "LCSC")
      )
      (libsource (lib "altium-import") (part "root_1_8MHz_"))
    )
    (comp (ref "X5")
      (value "SX3B12.288F1210F30")
      (fields (field (name "BOM_SUPPLIER PART") "C2901654") (field (name "CONTRIBUTOR") "LCSC"))
      (libsource (lib "altium-import") (part "root_1_SX3B12.288F1210F30_"))
    )
  )
  (nets
    (net (code "1") (name "/ACT") (class "Default")
      (node (ref "J1") (pin "11") (pinfunction "11_11") (pintype "passive"))
      (node (ref "U8") (pin "14") (pinfunction "ACT_14") (pintype "passive"))
    )
    (net (code "2") (name "/AVDD") (class "Default")
      (node (ref "C46") (pin "2") (pinfunction "2_2") (pintype "passive"))
      (node (ref "C58") (pin "2") (pinfunction "2_2") (pintype "passive"))
      (node (ref "C59") (pin "2") (pinfunction "2_2") (pintype "passive"))
      (node (ref "C60") (pin "2") (pinfunction "2_2") (pintype "passive"))
      (node (ref "R36") (pin "1") (pinfunction "1_1") (pintype "passive"))
      (node (ref "U5") (pin "38") (pinfunction "AVDD0_38") (pintype "passive"))
      (node (ref "U5") (pin "43") (pinfunction "AVDD1_43") (pintype "passive"))
      (node (ref "U5") (pin "45") (pinfunction "AVDD2_45") (pintype "passive"))
    )
    (net (code "3") (name "/BLK") (class "Default")
      (node (ref "R50") (pin "1") (pinfunction "1_1") (pintype "passive"))
      (node (ref "U1") (pin "19") (pinfunction "PB1_19") (pintype "passive"))
    )
    (net (code "4") (name "/BT_M{slash}S") (class "Default")
      (node (ref "U1") (pin "14") (pinfunction "PA4_14") (pintype "passive"))
      (node (ref "U2") (pin "12") (pinfunction "ROLE_12") (pintype "passive"))
    )
    (net (code "5") (name "/CFG0") (class "Default")
      (node (ref "R28") (pin "2") (pinfunction "2_2") (pintype "passive"))
      (node (ref "SW5") (pin "5") (pinfunction "5_5") (pintype "passive"))
      (node (ref "U8") (pin "26") (pinfunction "CFG0_26") (pintype "passive"))
    )
    (net (code "6") (name "/CVDD") (class "Default")
      (node (ref "C49") (pin "2") (pinfunction "2_2") (pintype "passive"))
      (node (ref "C61") (pin "2") (pinfunction "2_2") (pintype "passive"))
      (node (ref "C62") (pin "2") (pinfunction "2_2") (pintype "passive"))
      (node (ref "C63") (pin "2") (pinfunction "2_2") (pintype "passive"))
      (node (ref "C64") (pin "2") (pinfunction "2_2") (pintype "passive"))
      (node (ref "U12") (pin "2") (pinfunction "VOUT_2") (pintype "passive"))
      (node (ref "U12") (pin "4") (pinfunction "VOUT_4") (pintype "passive"))
      (node (ref "U5") (pin "24") (pinfunction "CVDD2_24") (pintype "passive"))
      (node (ref "U5") (pin "31") (pinfunction "CVDD3_31") (pintype "passive"))
      (node (ref "U5") (pin "5") (pinfunction "CVDD0_5") (pintype "passive"))
      (node (ref "U5") (pin "7") (pinfunction "CVDD1_7") (pintype "passive"))
    )
    (net (code "7") (name "/D+") (class "Default")
      (node (ref "R14") (pin "2") (pinfunction "2_2") (pintype "passive"))
      (node (ref "R21") (pin "1") (pinfunction "1_1") (pintype "passive"))
      (node (ref "USB2") (pin "6") (pinfunction "DP1_6") (pintype "passive"))
      (node (ref "USB2") (pin "8") (pinfunction "DP2_8") (pintype "passive"))
    )
    (net (code "8") (name "/D-") (class "Default")
      (node (ref "R20") (pin "1") (pinfunction "1_1") (pintype "passive"))
      (node (ref "USB2") (pin "5") (pinfunction "DN2_5") (pintype "passive"))
      (node (ref "USB2") (pin "7") (pinfunction "DN1_7") (pintype "passive"))
    )
    (net (code "9") (name "/F CS") (class "Default")
      (node (ref "U1") (pin "2") (pinfunction "PC13_2") (pintype "passive"))
      (node (ref "U11") (pin "1") (pinfunction "CS#_1") (pintype "passive"))
    )
    (net (code "10") (name "/GBUF") (class "Default")
      (node (ref "AUDIO1") (pin "1") (pinfunction "1_1") (pintype "passive"))
      (node (ref "R38") (pin "1") (pinfunction "1_1") (pintype "passive"))
      (node (ref "U5") (pin "42") (pinfunction "GBUF_42") (pintype "passive"))
    )
    (net (code "11") (name "/IIC SCL") (class "Default")
      (node (ref "R48") (pin "2") (pinfunction "2_2") (pintype "passive"))
      (node (ref "U1") (pin "45") (pinfunction "PB8_45") (pintype "passive"))
      (node (ref "U4") (pin "4") (pinfunction "SCK_4") (pintype "passive"))
      (node (ref "U6") (pin "6") (pinfunction "SCL_6") (pintype "passive"))
      (node (ref "U9") (pin "2") (pinfunction "SCL_2") (pintype "passive"))
    )
    (net (code "12") (name "/IIC SDA") (class "Default")
      (node (ref "R46") (pin "2") (pinfunction "2_2") (pintype "passive"))
      (node (ref "U1") (pin "46") (pinfunction "PB9_46") (pintype "passive"))
      (node (ref "U4") (pin "3") (pinfunction "SDI_3") (pintype "passive"))
      (node (ref "U6") (pin "5") (pinfunction "SDA_5") (pintype "passive"))
      (node (ref "U9") (pin "3") (pinfunction "SDA_3") (pintype "passive"))
    )
    (net (code "13") (name "/INT_RSET") (class "Default")
      (node (ref "SW5") (pin "4") (pinfunction "4_4") (pintype "passive"))
      (node (ref "U8") (pin "27") (pinfunction "RSET_27") (pintype "passive"))
    )
    (net (code "14") (name "/IO_VDD") (class "Default")
      (node (ref "C52") (pin "2") (pinfunction "2_2") (pintype "passive"))
      (node (ref "C53") (pin "2") (pinfunction "2_2") (pintype "passive"))
      (node (ref "C57") (pin "2") (pinfunction "2_2") (pintype "passive"))
      (node (ref "R10") (pin "1") (pinfunction "1_1") (pintype "passive"))
      (node (ref "R18") (pin "2") (pinfunction "2_2") (pintype "passive"))
      (node (ref "U5") (pin "14") (pinfunction "IOVDD1_14") (pintype "passive"))
      (node (ref "U5") (pin "19") (pinfunction "IOVDD2_19") (pintype "passive"))
      (node (ref "U5") (pin "32") (pinfunction "XTEST_32") (pintype "passive"))
      (node (ref "U5") (pin "6") (pinfunction "IOVDD0_6") (pintype "passive"))
    )
    (net (code "15") (name "/KEY1") (class "Default")
      (node (ref "SW4") (pin "1") (pinfunction "1_1") (pintype "passive"))
      (node (ref "U1") (pin "10") (pinfunction "PA0_10") (pintype "passive"))
    )
    (net (code "16") (name "/KEY2") (class "Default")
      (node (ref "SW3") (pin "1") (pinfunction "1_1") (pintype "passive"))
      (node (ref "U1") (pin "18") (pinfunction "PB0_18") (pintype "passive"))
    )
    (net (code "17") (name "/LCD CS") (class "Default")
      (node (ref "U1") (pin "21") (pinfunction "PB10_21") (pintype "passive"))
      (node (ref "U10") (pin "7") (pinfunction "CS_7") (pintype "passive"))
    )
    (net (code "18") (name "/LCD DC") (class "Default")
      (node (ref "U1") (pin "27") (pinfunction "PB14_27") (pintype "passive"))
      (node (ref "U10") (pin "5") (pinfunction "RS_5") (pintype "passive"))
    )
    (net (code "19") (name "/LCD RES") (class "Default")
      (node (ref "U1") (pin "25") (pinfunction "PB12_25") (pintype "passive"))
      (node (ref "U10") (pin "6") (pinfunction "RES_6") (pintype "passive"))
    )
    (net (code "20") (name "/LCD SCL") (class "Default")
      (node (ref "U1") (pin "26") (pinfunction "PB13_26") (pintype "passive"))
      (node (ref "U10") (pin "4") (pinfunction "SCL_4") (pintype "passive"))
    )
    (net (code "21") (name "/LCD SDA") (class "Default")
      (node (ref "U1") (pin "11") (pinfunction "PA1_11") (pintype "passive"))
      (node (ref "U10") (pin "3") (pinfunction "SDA_3") (pintype "passive"))
    )
    (net (code "22") (name "/LED1") (class "Default")
      (node (ref "LED6") (pin "2") (pinfunction "C_2") (pintype "passive"))
      (node (ref "U1") (pin "42") (pinfunction "PB6_42") (pintype "passive"))
    )
    (net (code "23") (name "/LEDK") (class "Default")
      (node (ref "R49") (pin "2") (pinfunction "2_2") (pintype "passive"))
      (node (ref "U10") (pin "11") (pinfunction "LEDK_11") (pintype "passive"))
    )
    (net (code "24") (name "/LED_STLINK") (class "Default")
      (node (ref "LED2") (pin "2") (pinfunction "2_2") (pintype "passive"))
      (node (ref "U7") (pin "30") (pinfunction "PA9_30") (pintype "passive"))
    )
    (net (code "25") (name "/LINK") (class "Default")
      (node (ref "J1") (pin "10") (pinfunction "10_10") (pintype "passive"))
      (node (ref "U8") (pin "15") (pinfunction "LINK_15") (pintype "passive"))
    )
    (net (code "26") (name "/MCU_RX6") (class "Default")
      (node (ref "SW2") (pin "5") (pinfunction "B4_5") (pintype "passive"))
      (node (ref "TP2") (pin "3") (pinfunction "RX_3") (pintype "passive"))
      (node (ref "U8") (pin "7") (pinfunction "TXD_7") (pintype "passive"))
    )
    (net (code "27") (name "/MCU_TX") (class "Default")
      (node (ref "U1") (pin "38") (pinfunction "PA15_38") (pintype "passive"))
      (node (ref "U5") (pin "3") (pinfunction "XRESET_3") (pintype "passive"))
      (node (ref "U7") (pin "13") (pinfunction "PA3_13") (pintype "passive"))
    )
    (net (code "28") (name "/MCU_TX2") (class "Default")
      (node (ref "U1") (pin "12") (pinfunction "PA2_12") (pintype "passive"))
      (node (ref "U2") (pin "6") (pinfunction "RXD_6") (pintype "passive"))
      (node (ref "U5") (pin "23") (pinfunction "XCS_23") (pintype "passive"))
    )
    (net (code "29") (name "/MCU_TX6") (class "Default")
      (node (ref "SW2") (pin "8") (pinfunction "B1_8") (pintype "passive"))
      (node (ref "TP2") (pin "2") (pinfunction "TX_2") (pintype "passive"))
      (node (ref "U8") (pin "6") (pinfunction "RXD_6") (pintype "passive"))
    )
    (net (code "30") (name "/MP3_LEFT") (class "Default")
      (node (ref "AUDIO1") (pin "2") (pinfunction "2_2") (pintype "passive"))
      (node (ref "R51") (pin "1") (pinfunction "1_1") (pintype "passive"))
      (node (ref "U5") (pin "46") (pinfunction "LEFT_46") (pintype "passive"))
    )
    (net (code "31") (name "/MP3_RIGHT") (class "Default")
      (node (ref "AUDIO1") (pin "3") (pinfunction "3_3") (pintype "passive"))
      (node (ref "R52") (pin "1") (pinfunction "1_1") (pintype "passive"))
      (node (ref "U5") (pin "39") (pinfunction "RIGHT_39") (pintype "passive"))
    )
    (net (code "32") (name "/MUC_RX") (class "Default")
      (node (ref "U1") (pin "31") (pinfunction "PA10_31") (pintype "passive"))
      (node (ref "U5") (pin "8") (pinfunction "DREQ_8") (pintype "passive"))
      (node (ref "U7") (pin "12") (pinfunction "PA2_12") (pintype "passive"))
    )
    (net (code "33") (name "/MUC_RX2") (class "Default")
      (node (ref "U1") (pin "13") (pinfunction "PA3_13") (pintype "passive"))
      (node (ref "U2") (pin "7") (pinfunction "TXD_7") (pintype "passive"))
      (node (ref "U5") (pin "13") (pinfunction "XDCSBSYNC1_13") (pintype "passive"))
    )
    (net (code "34") (name "/NRST") (class "Default")
      (node (ref "C5") (pin "2") (pinfunction "2_2") (pintype "passive"))
      (node (ref "R5") (pin "2") (pinfunction "2_2") (pintype "passive"))
      (node (ref "SW1") (pin "1") (pinfunction "1_1") (pintype "passive"))
      (node (ref "U1") (pin "7") (pinfunction "NRST_7") (pintype "passive"))
      (node (ref "U7") (pin "18") (pinfunction "PB0_18") (pintype "passive"))
    )
    (net (code "35") (name "/PA11") (class "Default")
      (node (ref "SW2") (pin "1") (pinfunction "A1_1") (pintype "passive"))
      (node (ref "SW2") (pin "2") (pinfunction "A2_2") (pintype "passive"))
      (node (ref "U1") (pin "32") (pinfunction "PA11_32") (pintype "passive"))
    )
    (net (code "36") (name "/PA12") (class "Default")
      (node (ref "SW2") (pin "3") (pinfunction "A3_3") (pintype "passive"))
      (node (ref "SW2") (pin "4") (pinfunction "A4_4") (pintype "passive"))
      (node (ref "U1") (pin "33") (pinfunction "PA12_33") (pintype "passive"))
    )
    (net (code "37") (name "/RESTI") (class "Default")
      (node (ref "SW5") (pin "6") (pinfunction "6_6") (pintype "passive"))
      (node (ref "U8") (pin "16") (pinfunction "RSTI_16") (pintype "passive"))
    )
    (net (code "38") (name "/RXN") (class "Default")
      (node (ref "J1") (pin "6") (pinfunction "RD-_6") (pintype "passive"))
      (node (ref "U8") (pin "9") (pinfunction "RXN_9") (pintype "passive"))
    )
    (net (code "39") (name "/RXP") (class "Default")
      (node (ref "J1") (pin "3") (pinfunction "RD+_3") (pintype "passive"))
      (node (ref "U8") (pin "8") (pinfunction "RXP_8") (pintype "passive"))
    )
    (net (code "40") (name "/SDIO_CK") (class "Default")
      (node (ref "CARD1") (pin "5") (pinfunction "CLX_5") (pintype "passive"))
      (node (ref "U1") (pin "28") (pinfunction "PB15_28") (pintype "passive"))
    )
    (net (code "41") (name "/SDIO_CMD") (class "Default")
      (node (ref "CARD1") (pin "3") (pinfunction "CMD_3") (pintype "passive"))
      (node (ref "R29") (pin "2") (pinfunction "2_2") (pintype "passive"))
      (node (ref "U1") (pin "16") (pinfunction "PA6_16") (pintype "passive"))
    )
    (net (code "42") (name "/SDIO_D0") (class "Default")
      (node (ref "CARD1") (pin "7") (pinfunction "DAT0_7") (pintype "passive"))
      (node (ref "R19") (pin "1") (pinfunction "1_1") (pintype "passive"))
      (node (ref "U1") (pin "43") (pinfunction "PB7_43") (pintype "passive"))
    )
    (net (code "43") (name "/SDIO_D1") (class "Default")
      (node (ref "CARD1") (pin "8") (pinfunction "DAT1_8") (pintype "passive"))
      (node (ref "R35") (pin "1") (pinfunction "1_1") (pintype "passive"))
      (node (ref "U1") (pin "29") (pinfunction "PA8_29") (pintype "passive"))
    )
    (net (code "44") (name "/SDIO_D2") (class "Default")
      (node (ref "CARD1") (pin "1") (pinfunction "DAT2_1") (pintype "passive"))
      (node (ref "R4") (pin "2") (pinfunction "2_2") (pintype "passive"))
      (node (ref "U1") (pin "30") (pinfunction "PA9_30") (pintype "passive"))
    )
    (net (code "45") (name "/SDIO_D3") (class "Default")
      (node (ref "CARD1") (pin "2") (pinfunction "CD/DAT3_2") (pintype "passive"))
      (node (ref "R17") (pin "2") (pinfunction "2_2") (pintype "passive"))
      (node (ref "U1") (pin "41") (pinfunction "PB5_41") (pintype "passive"))
    )
    (net (code "46") (name "/SPI1 MISO") (class "Default")
      (node (ref "U1") (pin "40") (pinfunction "PB4_40") (pintype "passive"))
      (node (ref "U11") (pin "2") (pinfunction "DO(IO1)_2") (pintype "passive"))
      (node (ref "U5") (pin "30") (pinfunction "SO_30") (pintype "passive"))
    )
    (net (code "47") (name "/SPI1 MOSI") (class "Default")
      (node (ref "U1") (pin "17") (pinfunction "PA7_17") (pintype "passive"))
      (node (ref "U11") (pin "5") (pinfunction "DI(IO0)_5") (pintype "passive"))
      (node (ref "U5") (pin "29") (pinfunction "SI_29") (pintype "passive"))
    )
    (net (code "48") (name "/SPI1 SCK") (class "Default")
      (node (ref "U1") (pin "15") (pinfunction "PA5_15") (pintype "passive"))
      (node (ref "U11") (pin "6") (pinfunction "CLK_6") (pintype "passive"))
      (node (ref "U5") (pin "28") (pinfunction "SCLK_28") (pintype "passive"))
    )
    (net (code "49") (name "/STL USB D+") (class "Default")
      (node (ref "R21") (pin "2") (pinfunction "2_2") (pintype "passive"))
      (node (ref "U7") (pin "33") (pinfunction "PA12_33") (pintype "passive"))
    )
    (net (code "50") (name "/STL USB D-") (class "Default")
      (node (ref "R20") (pin "2") (pinfunction "2_2") (pintype "passive"))
      (node (ref "U7") (pin "32") (pinfunction "PA11_32") (pintype "passive"))
    )
    (net (code "51") (name "/ST_SWCLK") (class "Default")
      (node (ref "TP1") (pin "2") (pinfunction "SCLK_2") (pintype "passive"))
      (node (ref "U7") (pin "37") (pinfunction "PA14_37") (pintype "passive"))
    )
    (net (code "52") (name "/ST_SWDIO") (class "Default")
      (node (ref "TP1") (pin "3") (pinfunction "SDIO_3") (pintype "passive"))
      (node (ref "U7") (pin "34") (pinfunction "PA13_34") (pintype "passive"))
    )
    (net (code "53") (name "/TXN") (class "Default")
      (node (ref "J1") (pin "2") (pinfunction "TD-_2") (pintype "passive"))
      (node (ref "U8") (pin "11") (pinfunction "TXN_11") (pintype "passive"))
    )
    (net (code "54") (name "/TXP") (class "Default")
      (node (ref "J1") (pin "1") (pinfunction "TD+_1") (pintype "passive"))
      (node (ref "U8") (pin "10") (pinfunction "TXP_10") (pintype "passive"))
    )
    (net (code "55") (name "/T_JTCK_SWCLK") (class "Default")
      (node (ref "U1") (pin "37") (pinfunction "PA14_37") (pintype "passive"))
      (node (ref "U7") (pin "15") (pinfunction "PA5_15") (pintype "passive"))
      (node (ref "U7") (pin "26") (pinfunction "PB13_26") (pintype "passive"))
    )
    (net (code "56") (name "/T_JTMS_SWDIO") (class "Default")
      (node (ref "R43") (pin "2") (pinfunction "2_2") (pintype "passive"))
      (node (ref "U1") (pin "34") (pinfunction "PA13_34") (pintype "passive"))
      (node (ref "U7") (pin "27") (pinfunction "PB14_27") (pintype "passive"))
    )
    (net (code "57") (name "/T_SWDIO_IN") (class "Default")
      (node (ref "R43") (pin "1") (pinfunction "1_1") (pintype "passive"))
      (node (ref "U7") (pin "25") (pinfunction "PB12_25") (pintype "passive"))
    )
    (net (code "58") (name "/T_SWO") (class "Default")
      (node (ref "U1") (pin "39") (pinfunction "PB3_39") (pintype "passive"))
      (node (ref "U7") (pin "31") (pinfunction "PA10_31") (pintype "passive"))
    )
    (net (code "59") (name "/USB D+") (class "Default")
      (node (ref "R25") (pin "1") (pinfunction "1_1") (pintype "passive"))
      (node (ref "R8") (pin "2") (pinfunction "2_2") (pintype "passive"))
      (node (ref "SW2") (pin "6") (pinfunction "B3_6") (pintype "passive"))
    )
    (net (code "60") (name "/USB D-") (class "Default")
      (node (ref "R11") (pin "2") (pinfunction "2_2") (pintype "passive"))
      (node (ref "SW2") (pin "7") (pinfunction "B2_7") (pintype "passive"))
    )
    (net (code "61") (name "/USB RENUMn") (class "Default")
      (node (ref "R40") (pin "2") (pinfunction "2_2") (pintype "passive"))
      (node (ref "U7") (pin "38") (pinfunction "PA15_38") (pintype "passive"))
    )
    (net (code "62") (name "/VCC") (class "Default")
      (node (ref "C38") (pin "1") (pinfunction "1_1") (pintype "passive"))
      (node (ref "C39") (pin "1") (pinfunction "1_1") (pintype "passive"))
      (node (ref "C40") (pin "1") (pinfunction "1_1") (pintype "passive"))
      (node (ref "U8") (pin "22") (pinfunction "VCC_22") (pintype "passive"))
      (node (ref "U8") (pin "3") (pinfunction "VCC_3") (pintype "passive"))
      (node (ref "U8") (pin "4") (pinfunction "VCC_4") (pintype "passive"))
    )
    (net (code "63") (name "3V3") (class "Default")
      (node (ref "C1") (pin "1") (pinfunction "1_1") (pintype "passive"))
      (node (ref "C11") (pin "1") (pinfunction "1_1") (pintype "passive"))
      (node (ref "C13") (pin "1") (pinfunction "1_1") (pintype "passive"))
      (node (ref "C14") (pin "2") (pinfunction "2_2") (pintype "passive"))
      (node (ref "C15") (pin "2") (pinfunction "2_2") (pintype "passive"))
      (node (ref "C16") (pin "2") (pinfunction "2_2") (pintype "passive"))
      (node (ref "C17") (pin "2") (pinfunction "2_2") (pintype "passive"))
      (node (ref "C19") (pin "2") (pinfunction "2_2") (pintype "passive"))
      (node (ref "C2") (pin "2") (pinfunction "2_2") (pintype "passive"))
      (node (ref "C20") (pin "2") (pinfunction "2_2") (pintype "passive"))
      (node (ref "C22") (pin "2") (pinfunction "2_2") (pintype "passive"))
      (node (ref "C24") (pin "2") (pinfunction "2_2") (pintype "passive"))
      (node (ref "C25") (pin "1") (pinfunction "1_1") (pintype "passive"))
      (node (ref "C27") (pin "1") (pinfunction "1_1") (pintype "passive"))
      (node (ref "C32") (pin "2") (pinfunction "2_2") (pintype "passive"))
      (node (ref "C33") (pin "2") (pinfunction "2_2") (pintype "passive"))
      (node (ref "C34") (pin "2") (pinfunction "2_2") (pintype "passive"))
      (node (ref "C35") (pin "1") (pinfunction "1_1") (pintype "passive"))
      (node (ref "C36") (pin "1") (pinfunction "1_1") (pintype "passive"))
      (node (ref "C37") (pin "2") (pinfunction "2_2") (pintype "passive"))
      (node (ref "C42") (pin "2") (pinfunction "2_2") (pintype "passive"))
      (node (ref "C43") (pin "2") (pinfunction "2_2") (pintype "passive"))
      (node (ref "C44") (pin "2") (pinfunction "2_2") (pintype "passive"))
      (node (ref "C48") (pin "2") (pinfunction "2_2") (pintype "passive"))
      (node (ref "C7") (pin "2") (pinfunction "2_2") (pintype "passive"))
      (node (ref "C9") (pin "2") (pinfunction "2_2") (pintype "passive"))
      (node (ref "CARD1") (pin "4") (pinfunction "VDD_4") (pintype "passive"))
      (node (ref "J1") (pin "4") (pinfunction "4_4") (pintype "passive"))
      (node (ref "J1") (pin "5") (pinfunction "5_5") (pintype "passive"))
      (node (ref "L1") (pin "2") (pinfunction "2_2") (pintype "passive"))
      (node (ref "L2") (pin "1") (pinfunction "1_1") (pintype "passive"))
      (node (ref "Q1") (pin "3") (pinfunction "C_3") (pintype "passive"))
      (node (ref "R10") (pin "2") (pinfunction "2_2") (pintype "passive"))
      (node (ref "R12") (pin "2") (pinfunction "2_2") (pintype "passive"))
      (node (ref "R16") (pin "1") (pinfunction "1_1") (pintype "passive"))
      (node (ref "R17") (pin "1") (pinfunction "1_1") (pintype "passive"))
      (node (ref "R19") (pin "2") (pinfunction "2_2") (pintype "passive"))
      (node (ref "R22") (pin "1") (pinfunction "1_1") (pintype "passive"))
      (node (ref "R23") (pin "1") (pinfunction "1_1") (pintype "passive"))
      (node (ref "R25") (pin "2") (pinfunction "2_2") (pintype "passive"))
      (node (ref "R26") (pin "2") (pinfunction "2_2") (pintype "passive"))
      (node (ref "R27") (pin "2") (pinfunction "2_2") (pintype "passive"))
      (node (ref "R28") (pin "1") (pinfunction "1_1") (pintype "passive"))
      (node (ref "R29") (pin "1") (pinfunction "1_1") (pintype "passive"))
      (node (ref "R31") (pin "2") (pinfunction "2_2") (pintype "passive"))
      (node (ref "R35") (pin "2") (pinfunction "2_2") (pintype "passive"))
      (node (ref "R36") (pin "2") (pinfunction "2_2") (pintype "passive"))
      (node (ref "R37") (pin "2") (pinfunction "2_2") (pintype "passive"))
      (node (ref "R4") (pin "1") (pinfunction "1_1") (pintype "passive"))
      (node (ref "R41") (pin "1") (pinfunction "1_1") (pintype "passive"))
      (node (ref "R45") (pin "1") (pinfunction "1_1") (pintype "passive"))
      (node (ref "R46") (pin "1") (pinfunction "1_1") (pintype "passive"))
      (node (ref "R47") (pin "2") (pinfunction "2_2") (pintype "passive"))
      (node (ref "R48") (pin "1") (pinfunction "1_1") (pintype "passive"))
      (node (ref "R5") (pin "1") (pinfunction "1_1") (pintype "passive"))
      (node (ref "SW4") (pin "2") (pinfunction "2_2") (pintype "passive"))
      (node (ref "TP1") (pin "1") (pinfunction "VCC_1") (pintype "passive"))
      (node (ref "TP2") (pin "1") (pinfunction "VCC_1") (pintype "passive"))
      (node (ref "U1") (pin "1") (pinfunction "VBAT_1") (pintype "passive"))
      (node (ref "U1") (pin "24") (pinfunction "VDD_24") (pintype "passive"))
      (node (ref "U1") (pin "36") (pinfunction "VDD_36") (pintype "passive"))
      (node (ref "U1") (pin "48") (pinfunction "VDD_48") (pintype "passive"))
      (node (ref "U10") (pin "10") (pinfunction "VCC_10") (pintype "passive"))
      (node (ref "U10") (pin "12") (pinfunction "LEDA_12") (pintype "passive"))
      (node (ref "U11") (pin "3") (pinfunction "WP#(IO2)_3") (pintype "passive"))
      (node (ref "U11") (pin "7") (pinfunction "HOLD#_or_RESET#(IO3)_7") (pintype "passive"))
      (node (ref "U11") (pin "8") (pinfunction "VCC_8") (pintype "passive"))
      (node (ref "U2") (pin "5") (pinfunction "3V3_5") (pintype "passive"))
      (node (ref "U3") (pin "5") (pinfunction "VOS_5") (pintype "passive"))
      (node (ref "U4") (pin "2") (pinfunction "CSB_2") (pintype "passive"))
      (node (ref "U4") (pin "6") (pinfunction "VDDIO_6") (pintype "passive"))
      (node (ref "U4") (pin "8") (pinfunction "VDD_8") (pintype "passive"))
      (node (ref "U6") (pin "8") (pinfunction "VCC_8") (pintype "passive"))
      (node (ref "U7") (pin "1") (pinfunction "VBAT_1") (pintype "passive"))
      (node (ref "U7") (pin "24") (pinfunction "VDD_1_24") (pintype "passive"))
      (node (ref "U7") (pin "36") (pinfunction "VDD_2_36") (pintype "passive"))
      (node (ref "U7") (pin "48") (pinfunction "VDD_3_48") (pintype "passive"))
      (node (ref "U7") (pin "9") (pinfunction "VDDA_9") (pintype "passive"))
      (node (ref "U8") (pin "5") (pinfunction "VDD_5") (pintype "passive"))
      (node (ref "U9") (pin "1") (pinfunction "VCC_1") (pintype "passive"))
    )
    (net (code "64") (name "GND") (class "Default")
      (node (ref "C1") (pin "2") (pinfunction "2_2") (pintype "passive"))
      (node (ref "C10") (pin "1") (pinfunction "1_1") (pintype "passive"))
      (node (ref "C11") (pin "2") (pinfunction "2_2") (pintype "passive"))
      (node (ref "C12") (pin "1") (pinfunction "1_1") (pintype "passive"))
      (node (ref "C13") (pin "2") (pinfunction "2_2") (pintype "passive"))
      (node (ref "C14") (pin "1") (pinfunction "1_1") (pintype "passive"))
      (node (ref "C15") (pin "1") (pinfunction "1_1") (pintype "passive"))
      (node (ref "C16") (pin "1") (pinfunction "1_1") (pintype "passive"))
      (node (ref "C17") (pin "1") (pinfunction "1_1") (pintype "passive"))
      (node (ref "C18") (pin "1") (pinfunction "1_1") (pintype "passive"))
      (node (ref "C19") (pin "1") (pinfunction "1_1") (pintype "passive"))
      (node (ref "C2") (pin "1") (pinfunction "1_1") (pintype "passive"))
      (node (ref "C20") (pin "1") (pinfunction "1_1") (pintype "passive"))
      (node (ref "C21") (pin "1") (pinfunction "1_1") (pintype "passive"))
      (node (ref "C22") (pin "1") (pinfunction "1_1") (pintype "passive"))
      (node (ref "C23") (pin "2") (pinfunction "2_2") (pintype "passive"))
      (node (ref "C24") (pin "1") (pinfunction "1_1") (pintype "passive"))
      (node (ref "C25") (pin "2") (pinfunction "2_2") (pintype "passive"))
      (node (ref "C26") (pin "2") (pinfunction "2_2") (pintype "passive"))
      (node (ref "C27") (pin "2") (pinfunction "2_2") (pintype "passive"))
      (node (ref "C28") (pin "1") (pinfunction "1_1") (pintype "passive"))
      (node (ref "C3") (pin "2") (pinfunction "2_2") (pintype "passive"))
      (node (ref "C30") (pin "1") (pinfunction "1_1") (pintype "passive"))
      (node (ref "C31") (pin "1") (pinfunction "1_1") (pintype "passive"))
      (node (ref "C32") (pin "1") (pinfunction "1_1") (pintype "passive"))
      (node (ref "C33") (pin "1") (pinfunction "1_1") (pintype "passive"))
      (node (ref "C34") (pin "1") (pinfunction "1_1") (pintype "passive"))
      (node (ref "C35") (pin "2") (pinfunction "2_2") (pintype "passive"))
      (node (ref "C36") (pin "2") (pinfunction "2_2") (pintype "passive"))
      (node (ref "C37") (pin "1") (pinfunction "1_1") (pintype "passive"))
      (node (ref "C38") (pin "2") (pinfunction "2_2") (pintype "passive"))
      (node (ref "C39") (pin "2") (pinfunction "2_2") (pintype "passive"))
      (node (ref "C4") (pin "1") (pinfunction "1_1") (pintype "passive"))
      (node (ref "C40") (pin "2") (pinfunction "2_2") (pintype "passive"))
      (node (ref "C41") (pin "1") (pinfunction "1_1") (pintype "passive"))
      (node (ref "C42") (pin "1") (pinfunction "1_1") (pintype "passive"))
      (node (ref "C43") (pin "1") (pinfunction "1_1") (pintype "passive"))
      (node (ref "C44") (pin "1") (pinfunction "1_1") (pintype "passive"))
      (node (ref "C45") (pin "1") (pinfunction "1_1") (pintype "passive"))
      (node (ref "C46") (pin "1") (pinfunction "1_1") (pintype "passive"))
      (node (ref "C47") (pin "1") (pinfunction "1_1") (pintype "passive"))
      (node (ref "C48") (pin "1") (pinfunction "1_1") (pintype "passive"))
      (node (ref "C49") (pin "1") (pinfunction "1_1") (pintype "passive"))
      (node (ref "C5") (pin "1") (pinfunction "1_1") (pintype "passive"))
      (node (ref "C50") (pin "1") (pinfunction "1_1") (pintype "passive"))
      (node (ref "C51") (pin "1") (pinfunction "1_1") (pintype "passive"))
      (node (ref "C52") (pin "1") (pinfunction "1_1") (pintype "passive"))
      (node (ref "C53") (pin "1") (pinfunction "1_1") (pintype "passive"))
      (node (ref "C54") (pin "2") (pinfunction "2_2") (pintype "passive"))
      (node (ref "C55") (pin "2") (pinfunction "2_2") (pintype "passive"))
      (node (ref "C56") (pin "2") (pinfunction "2_2") (pintype "passive"))
      (node (ref "C57") (pin "1") (pinfunction "1_1") (pintype "passive"))
      (node (ref "C58") (pin "1") (pinfunction "1_1") (pintype "passive"))
      (node (ref "C59") (pin "1") (pinfunction "1_1") (pintype "passive"))
      (node (ref "C6") (pin "2") (pinfunction "2_2") (pintype "passive"))
      (node (ref "C60") (pin "1") (pinfunction "1_1") (pintype "passive"))
      (node (ref "C61") (pin "1") (pinfunction "1_1") (pintype "passive"))
      (node (ref "C62") (pin "1") (pinfunction "1_1") (pintype "passive"))
      (node (ref "C63") (pin "1") (pinfunction "1_1") (pintype "passive"))
      (node (ref "C64") (pin "1") (pinfunction "1_1") (pintype "passive"))
      (node (ref "C7") (pin "1") (pinfunction "1_1") (pintype "passive"))
      (node (ref "C8") (pin "1") (pinfunction "1_1") (pintype "passive"))
      (node (ref "C9") (pin "1") (pinfunction "1_1") (pintype "passive"))
      (node (ref "CARD1") (pin "10") (pinfunction "10_10") (pintype "passive"))
      (node (ref "CARD1") (pin "6") (pinfunction "VSS_6") (pintype "passive"))
      (node (ref "CARD1") (pin "9") (pinfunction "9_9") (pintype "passive"))
      (node (ref "J1") (pin "SH1") (pinfunction "SH1_SH1") (pintype "passive"))
      (node (ref "J1") (pin "SH2") (pinfunction "SH2_SH2") (pintype "passive"))
      (node (ref "LED1") (pin "2") (pinfunction "C_2") (pintype "passive"))
      (node (ref "LED3") (pin "2") (pinfunction "C_2") (pintype "passive"))
      (node (ref "Q2") (pin "2") (pinfunction "E_2") (pintype "passive"))
      (node (ref "R13") (pin "2") (pinfunction "2_2") (pintype "passive"))
      (node (ref "R2") (pin "2") (pinfunction "2_2") (pintype "passive"))
      (node (ref "R24") (pin "2") (pinfunction "2_2") (pintype "passive"))
      (node (ref "R3") (pin "1") (pinfunction "1_1") (pintype "passive"))
      (node (ref "R30") (pin "2") (pinfunction "2_2") (pintype "passive"))
      (node (ref "R32") (pin "2") (pinfunction "2_2") (pintype "passive"))
      (node (ref "R33") (pin "2") (pinfunction "2_2") (pintype "passive"))
      (node (ref "R39") (pin "1") (pinfunction "1_1") (pintype "passive"))
      (node (ref "R42") (pin "2") (pinfunction "2_2") (pintype "passive"))
      (node (ref "R44") (pin "1") (pinfunction "1_1") (pintype "passive"))
      (node (ref "R6") (pin "2") (pinfunction "2_2") (pintype "passive"))
      (node (ref "R7") (pin "1") (pinfunction "1_1") (pintype "passive"))
      (node (ref "R9") (pin "1") (pinfunction "1_1") (pintype "passive"))
      (node (ref "SW1") (pin "2") (pinfunction "2_2") (pintype "passive"))
      (node (ref "SW3") (pin "2") (pinfunction "2_2") (pintype "passive"))
      (node (ref "SW5") (pin "1") (pinfunction "1_1") (pintype "passive"))
      (node (ref "SW5") (pin "2") (pinfunction "2_2") (pintype "passive"))
      (node (ref "SW5") (pin "3") (pinfunction "3_3") (pintype "passive"))
      (node (ref "TP1") (pin "4") (pinfunction "GND_4") (pintype "passive"))
      (node (ref "TP2") (pin "4") (pinfunction "GND_4") (pintype "passive"))
      (node (ref "U1") (pin "23") (pinfunction "VSS_23") (pintype "passive"))
      (node (ref "U1") (pin "35") (pinfunction "VSS_35") (pintype "passive"))
      (node (ref "U1") (pin "47") (pinfunction "VSS_47") (pintype "passive"))
      (node (ref "U1") (pin "49") (pinfunction "PAD_49") (pintype "passive"))
      (node (ref "U1") (pin "8") (pinfunction "VSSA/VREF-_8") (pintype "passive"))
      (node (ref "U10") (pin "13") (pinfunction "GND_13") (pintype "passive"))
      (node (ref "U10") (pin "8") (pinfunction "GND_8") (pintype "passive"))
      (node (ref "U11") (pin "4") (pinfunction "GND_4") (pintype "passive"))
      (node (ref "U11") (pin "9") (pinfunction "EP_9") (pintype "passive"))
      (node (ref "U12") (pin "1") (pinfunction "GND_1") (pintype "passive"))
      (node (ref "U2") (pin "8") (pinfunction "GND_8") (pintype "passive"))
      (node (ref "U2") (pin "9") (pinfunction "SLEEP_9") (pintype "passive"))
      (node (ref "U3") (pin "2") (pinfunction "GND_2") (pintype "passive"))
      (node (ref "U3") (pin "3") (pinfunction "MODE_3") (pintype "passive"))
      (node (ref "U3") (pin "9") (pinfunction "EP_9") (pintype "passive"))
      (node (ref "U4") (pin "1") (pinfunction "GND_1") (pintype "passive"))
      (node (ref "U4") (pin "5") (pinfunction "SDO_5") (pintype "passive"))
      (node (ref "U4") (pin "7") (pinfunction "GND_7") (pintype "passive"))
      (node (ref "U5") (pin "16") (pinfunction "DGND1_16") (pintype "passive"))
      (node (ref "U5") (pin "20") (pinfunction "DGND2_20") (pintype "passive"))
      (node (ref "U5") (pin "21") (pinfunction "DGND3_21") (pintype "passive"))
      (node (ref "U5") (pin "22") (pinfunction "DGND4_22") (pintype "passive"))
      (node (ref "U5") (pin "35") (pinfunction "GND_35") (pintype "passive"))
      (node (ref "U5") (pin "37") (pinfunction "AGND0_37") (pintype "passive"))
      (node (ref "U5") (pin "4") (pinfunction "DGND0_4") (pintype "passive"))
      (node (ref "U5") (pin "40") (pinfunction "AGND1_40") (pintype "passive"))
      (node (ref "U5") (pin "41") (pinfunction "AGND2_41") (pintype "passive"))
      (node (ref "U5") (pin "47") (pinfunction "AGND3_47") (pintype "passive"))
      (node (ref "U6") (pin "1") (pinfunction "A0_1") (pintype "passive"))
      (node (ref "U6") (pin "2") (pinfunction "A1_2") (pintype "passive"))
      (node (ref "U6") (pin "3") (pinfunction "A2_3") (pintype "passive"))
      (node (ref "U6") (pin "4") (pinfunction "GND_4") (pintype "passive"))
      (node (ref "U6") (pin "7") (pinfunction "WP_7") (pintype "passive"))
      (node (ref "U6") (pin "9") (pinfunction "EP_9") (pintype "passive"))
      (node (ref "U7") (pin "20") (pinfunction "PB2_20") (pintype "passive"))
      (node (ref "U7") (pin "23") (pinfunction "VSS_1_23") (pintype "passive"))
      (node (ref "U7") (pin "35") (pinfunction "VSS_2_35") (pintype "passive"))
      (node (ref "U7") (pin "47") (pinfunction "VSS_3_47") (pintype "passive"))
      (node (ref "U7") (pin "49") (pinfunction "EP_49") (pintype "passive"))
      (node (ref "U7") (pin "8") (pinfunction "VSSA_8") (pintype "passive"))
      (node (ref "U8") (pin "29") (pinfunction "EP_29") (pintype "passive"))
      (node (ref "U9") (pin "4") (pinfunction "VSS_4") (pintype "passive"))
      (node (ref "USB1") (pin "1") (pinfunction "GND_1") (pintype "passive"))
      (node (ref "USB1") (pin "16") (pinfunction "GND_16") (pintype "passive"))
      (node (ref "USB1") (pin "20") (pinfunction "GND_20") (pintype "passive"))
      (node (ref "USB1") (pin "21") (pinfunction "EH_21") (pintype "passive"))
      (node (ref "USB1") (pin "8") (pinfunction "GND_8") (pintype "passive"))
      (node (ref "USB1") (pin "9") (pinfunction "GND_9") (pintype "passive"))
      (node (ref "USB2") (pin "1") (pinfunction "GND_1") (pintype "passive"))
      (node (ref "USB2") (pin "12") (pinfunction "GND_12") (pintype "passive"))
      (node (ref "USB2") (pin "13") (pinfunction "GND_13") (pintype "passive"))
      (node (ref "USB2") (pin "14") (pinfunction "GND_14") (pintype "passive"))
      (node (ref "USB2") (pin "15") (pinfunction "GND_15") (pintype "passive"))
      (node (ref "USB2") (pin "16") (pinfunction "GND_16") (pintype "passive"))
      (node (ref "X2") (pin "2") (pinfunction "GND_2") (pintype "passive"))
      (node (ref "X2") (pin "4") (pinfunction "GND_4") (pintype "passive"))
      (node (ref "X3") (pin "2") (pinfunction "GND_2") (pintype "passive"))
      (node (ref "X3") (pin "4") (pinfunction "GND_4") (pintype "passive"))
      (node (ref "X4") (pin "2") (pinfunction "GND_2") (pintype "passive"))
      (node (ref "X4") (pin "4") (pinfunction "GND_4") (pintype "passive"))
      (node (ref "X5") (pin "2") (pinfunction "GND_2") (pintype "passive"))
      (node (ref "X5") (pin "4") (pinfunction "GND_4") (pintype "passive"))
    )
    (net (code "65") (name "Net-(C54-Pad1)") (class "Default")
      (node (ref "C54") (pin "1") (pinfunction "1_1") (pintype "passive"))
      (node (ref "R38") (pin "2") (pinfunction "2_2") (pintype "passive"))
    )
    (net (code "66") (name "Net-(C55-Pad1)") (class "Default")
      (node (ref "C55") (pin "1") (pinfunction "1_1") (pintype "passive"))
      (node (ref "R51") (pin "2") (pinfunction "2_2") (pintype "passive"))
    )
    (net (code "67") (name "Net-(C56-Pad1)") (class "Default")
      (node (ref "C56") (pin "1") (pinfunction "1_1") (pintype "passive"))
      (node (ref "R52") (pin "2") (pinfunction "2_2") (pintype "passive"))
    )
    (net (code "68") (name "Net-(J1-CHS_GND)") (class "Default")
      (node (ref "J1") (pin "8") (pinfunction "CHS_GND_8") (pintype "passive"))
      (node (ref "R9") (pin "2") (pinfunction "2_2") (pintype "passive"))
    )
    (net (code "69") (name "Net-(J1-Pad9)") (class "Default")
      (node (ref "J1") (pin "9") (pinfunction "9_9") (pintype "passive"))
      (node (ref "R16") (pin "2") (pinfunction "2_2") (pintype "passive"))
    )
    (net (code "70") (name "Net-(J1-Pad12)") (class "Default")
      (node (ref "J1") (pin "12") (pinfunction "12_12") (pintype "passive"))
      (node (ref "R22") (pin "2") (pinfunction "2_2") (pintype "passive"))
    )
    (net (code "71") (name "Net-(LED1-A)") (class "Default")
      (node (ref "LED1") (pin "1") (pinfunction "A_1") (pintype "passive"))
      (node (ref "R1") (pin "1") (pinfunction "1_1") (pintype "passive"))
    )
    (net (code "72") (name "Net-(LED2-Pad1)") (class "Default")
      (node (ref "LED2") (pin "1") (pinfunction "1_1") (pintype "passive"))
      (node (ref "R23") (pin "2") (pinfunction "2_2") (pintype "passive"))
    )
    (net (code "73") (name "Net-(LED3-A)") (class "Default")
      (node (ref "LED3") (pin "1") (pinfunction "A_1") (pintype "passive"))
      (node (ref "R12") (pin "1") (pinfunction "1_1") (pintype "passive"))
    )
    (net (code "74") (name "Net-(LED4-A)") (class "Default")
      (node (ref "LED4") (pin "1") (pinfunction "A_1") (pintype "passive"))
      (node (ref "R26") (pin "1") (pinfunction "1_1") (pintype "passive"))
    )
    (net (code "75") (name "Net-(LED4-C)") (class "Default")
      (node (ref "LED4") (pin "2") (pinfunction "C_2") (pintype "passive"))
      (node (ref "U8") (pin "17") (pinfunction "RUN_17") (pintype "passive"))
    )
    (net (code "76") (name "Net-(LED5-A)") (class "Default")
      (node (ref "LED5") (pin "1") (pinfunction "A_1") (pintype "passive"))
      (node (ref "R27") (pin "1") (pinfunction "1_1") (pintype "passive"))
    )
    (net (code "77") (name "Net-(LED5-C)") (class "Default")
      (node (ref "LED5") (pin "2") (pinfunction "C_2") (pintype "passive"))
      (node (ref "U8") (pin "28") (pinfunction "TXPCS_28") (pintype "passive"))
    )
    (net (code "78") (name "Net-(LED6-A)") (class "Default")
      (node (ref "LED6") (pin "1") (pinfunction "A_1") (pintype "passive"))
      (node (ref "R31") (pin "1") (pinfunction "1_1") (pintype "passive"))
    )
    (net (code "79") (name "Net-(Q1-B)") (class "Default")
      (node (ref "Q1") (pin "1") (pinfunction "B_1") (pintype "passive"))
      (node (ref "R34") (pin "1") (pinfunction "1_1") (pintype "passive"))
      (node (ref "R39") (pin "2") (pinfunction "2_2") (pintype "passive"))
      (node (ref "R40") (pin "1") (pinfunction "1_1") (pintype "passive"))
    )
    (net (code "80") (name "Net-(Q1-E)") (class "Default")
      (node (ref "Q1") (pin "2") (pinfunction "E_2") (pintype "passive"))
      (node (ref "R14") (pin "1") (pinfunction "1_1") (pintype "passive"))
    )
    (net (code "81") (name "Net-(Q2-B)") (class "Default")
      (node (ref "Q2") (pin "1") (pinfunction "B_1") (pintype "passive"))
      (node (ref "R47") (pin "1") (pinfunction "1_1") (pintype "passive"))
      (node (ref "R50") (pin "2") (pinfunction "2_2") (pintype "passive"))
    )
    (net (code "82") (name "Net-(Q2-C)") (class "Default")
      (node (ref "Q2") (pin "3") (pinfunction "C_3") (pintype "passive"))
      (node (ref "R49") (pin "1") (pinfunction "1_1") (pintype "passive"))
    )
    (net (code "83") (name "Net-(R8-Pad1)") (class "Default")
      (node (ref "R8") (pin "1") (pinfunction "1_1") (pintype "passive"))
      (node (ref "USB1") (pin "12") (pinfunction "D+_12") (pintype "passive"))
      (node (ref "USB1") (pin "19") (pinfunction "D+_19") (pintype "passive"))
      (node (ref "USB1") (pin "4") (pinfunction "D+_4") (pintype "passive"))
    )
    (net (code "84") (name "Net-(R11-Pad1)") (class "Default")
      (node (ref "R11") (pin "1") (pinfunction "1_1") (pintype "passive"))
      (node (ref "USB1") (pin "13") (pinfunction "D-_13") (pintype "passive"))
      (node (ref "USB1") (pin "18") (pinfunction "D-_18") (pintype "passive"))
      (node (ref "USB1") (pin "5") (pinfunction "D-_5") (pintype "passive"))
    )
    (net (code "85") (name "Net-(U1-BOOT0)") (class "Default")
      (node (ref "R3") (pin "2") (pinfunction "2_2") (pintype "passive"))
      (node (ref "U1") (pin "44") (pinfunction "BOOT0_44") (pintype "passive"))
    )
    (net (code "86") (name "Net-(U1-PB2)") (class "Default")
      (node (ref "R6") (pin "1") (pinfunction "1_1") (pintype "passive"))
      (node (ref "U1") (pin "20") (pinfunction "PB2_20") (pintype "passive"))
    )
    (net (code "87") (name "Net-(U1-PC14{slash}OSC32IN)") (class "Default")
      (node (ref "C23") (pin "1") (pinfunction "1_1") (pintype "passive"))
      (node (ref "U1") (pin "3") (pinfunction "PC14/OSC32IN_3") (pintype "passive"))
      (node (ref "X1") (pin "1") (pinfunction "OSC1_1") (pintype "passive"))
    )
    (net (code "88") (name "Net-(U1-PC15{slash}OSC32OUT)") (class "Default")
      (node (ref "C6") (pin "1") (pinfunction "1_1") (pintype "passive"))
      (node (ref "U1") (pin "4") (pinfunction "PC15/OSC32OUT_4") (pintype "passive"))
      (node (ref "X1") (pin "2") (pinfunction "OSC2_2") (pintype "passive"))
    )
    (net (code "89") (name "Net-(U1-PH0-OSC_IN)") (class "Default")
      (node (ref "C18") (pin "2") (pinfunction "2_2") (pintype "passive"))
      (node (ref "U1") (pin "5") (pinfunction "PH0-OSC_IN_5") (pintype "passive"))
      (node (ref "X2") (pin "3") (pinfunction "OUT_3") (pintype "passive"))
    )
    (net (code "90") (name "Net-(U1-PH1-OSC_OUT)") (class "Default")
      (node (ref "C8") (pin "2") (pinfunction "2_2") (pintype "passive"))
      (node (ref "U1") (pin "6") (pinfunction "PH1-OSC_OUT_6") (pintype "passive"))
      (node (ref "X2") (pin "1") (pinfunction "OE#_1") (pintype "passive"))
    )
    (net (code "91") (name "Net-(U1-VCAP1)") (class "Default")
      (node (ref "C4") (pin "2") (pinfunction "2_2") (pintype "passive"))
      (node (ref "U1") (pin "22") (pinfunction "VCAP1_22") (pintype "passive"))
    )
    (net (code "92") (name "Net-(U1-VDDA{slash}VREF+)") (class "Default")
      (node (ref "C26") (pin "1") (pinfunction "1_1") (pintype "passive"))
      (node (ref "L2") (pin "2") (pinfunction "2_2") (pintype "passive"))
      (node (ref "U1") (pin "9") (pinfunction "VDDA/VREF+_9") (pintype "passive"))
    )
    (net (code "93") (name "Net-(U2-STA)") (class "Default")
      (node (ref "R1") (pin "2") (pinfunction "2_2") (pintype "passive"))
      (node (ref "U2") (pin "4") (pinfunction "STA_4") (pintype "passive"))
    )
    (net (code "94") (name "Net-(U3-SW)") (class "Default")
      (node (ref "L1") (pin "1") (pinfunction "1_1") (pintype "passive"))
      (node (ref "U3") (pin "7") (pinfunction "SW_7") (pintype "passive"))
    )
    (net (code "95") (name "Net-(U5-GPIO0)") (class "Default")
      (node (ref "R24") (pin "1") (pinfunction "1_1") (pintype "passive"))
      (node (ref "U5") (pin "33") (pinfunction "GPIO0_33") (pintype "passive"))
      (node (ref "U5") (pin "34") (pinfunction "GPIO1_34") (pintype "passive"))
    )
    (net (code "96") (name "Net-(U5-RCAP)") (class "Default")
      (node (ref "C47") (pin "2") (pinfunction "2_2") (pintype "passive"))
      (node (ref "U5") (pin "44") (pinfunction "RCAP_44") (pintype "passive"))
    )
    (net (code "97") (name "Net-(U5-RX)") (class "Default")
      (node (ref "R18") (pin "1") (pinfunction "1_1") (pintype "passive"))
      (node (ref "U5") (pin "26") (pinfunction "RX_26") (pintype "passive"))
    )
    (net (code "98") (name "Net-(U5-XTALI)") (class "Default")
      (node (ref "C45") (pin "2") (pinfunction "2_2") (pintype "passive"))
      (node (ref "R15") (pin "1") (pinfunction "1_1") (pintype "passive"))
      (node (ref "U5") (pin "18") (pinfunction "XTALI_18") (pintype "passive"))
      (node (ref "X5") (pin "3") (pinfunction "3_3") (pintype "passive"))
    )
    (net (code "99") (name "Net-(U5-XTALO)") (class "Default")
      (node (ref "C10") (pin "2") (pinfunction "2_2") (pintype "passive"))
      (node (ref "R15") (pin "2") (pinfunction "2_2") (pintype "passive"))
      (node (ref "U5") (pin "17") (pinfunction "XTALO_17") (pintype "passive"))
      (node (ref "X5") (pin "1") (pinfunction "1_1") (pintype "passive"))
    )
    (net (code "100") (name "Net-(U7-BOOT0)") (class "Default")
      (node (ref "R44") (pin "2") (pinfunction "2_2") (pintype "passive"))
      (node (ref "U7") (pin "44") (pinfunction "BOOT0_44") (pintype "passive"))
    )
    (net (code "101") (name "Net-(U7-NRST)") (class "Default")
      (node (ref "C31") (pin "2") (pinfunction "2_2") (pintype "passive"))
      (node (ref "R37") (pin "1") (pinfunction "1_1") (pintype "passive"))
      (node (ref "U7") (pin "7") (pinfunction "NRST_7") (pintype "passive"))
    )
    (net (code "102") (name "Net-(U7-PA0-WKUP)") (class "Default")
      (node (ref "R41") (pin "2") (pinfunction "2_2") (pintype "passive"))
      (node (ref "R42") (pin "1") (pinfunction "1_1") (pintype "passive"))
      (node (ref "U7") (pin "10") (pinfunction "PA0-WKUP_10") (pintype "passive"))
    )
    (net (code "103") (name "Net-(U7-PB3)") (class "Default")
      (node (ref "R45") (pin "2") (pinfunction "2_2") (pintype "passive"))
      (node (ref "U7") (pin "39") (pinfunction "PB3_39") (pintype "passive"))
    )
    (net (code "104") (name "Net-(U7-PC13-TAMPER-RTC)") (class "Default")
      (node (ref "R13") (pin "1") (pinfunction "1_1") (pintype "passive"))
      (node (ref "U7") (pin "2") (pinfunction "PC13-TAMPER-RTC_2") (pintype "passive"))
    )
    (net (code "105") (name "Net-(U7-PC14-OSC32_IN)") (class "Default")
      (node (ref "R30") (pin "1") (pinfunction "1_1") (pintype "passive"))
      (node (ref "U7") (pin "3") (pinfunction "PC14-OSC32_IN_3") (pintype "passive"))
    )
    (net (code "106") (name "Net-(U7-PD0-OSC_IN)") (class "Default")
      (node (ref "C28") (pin "2") (pinfunction "2_2") (pintype "passive"))
      (node (ref "U7") (pin "5") (pinfunction "PD0-OSC_IN_5") (pintype "passive"))
      (node (ref "X4") (pin "3") (pinfunction "OUT_3") (pintype "passive"))
    )
    (net (code "107") (name "Net-(U7-PD1-OSC_OUT)") (class "Default")
      (node (ref "C30") (pin "2") (pinfunction "2_2") (pintype "passive"))
      (node (ref "U7") (pin "6") (pinfunction "PD1-OSC_OUT_6") (pintype "passive"))
      (node (ref "X4") (pin "1") (pinfunction "OE#_1") (pintype "passive"))
    )
    (net (code "108") (name "Net-(U8-VREF)") (class "Default")
      (node (ref "C41") (pin "2") (pinfunction "2_2") (pintype "passive"))
      (node (ref "U8") (pin "20") (pinfunction "VREF_20") (pintype "passive"))
    )
    (net (code "109") (name "Net-(U8-XI)") (class "Default")
      (node (ref "C12") (pin "2") (pinfunction "2_2") (pintype "passive"))
      (node (ref "U8") (pin "19") (pinfunction "XI_19") (pintype "passive"))
      (node (ref "X3") (pin "1") (pinfunction "1_1") (pintype "passive"))
    )
    (net (code "110") (name "Net-(U8-XO)") (class "Default")
      (node (ref "C21") (pin "2") (pinfunction "2_2") (pintype "passive"))
      (node (ref "U8") (pin "18") (pinfunction "XO_18") (pintype "passive"))
      (node (ref "X3") (pin "3") (pinfunction "3_3") (pintype "passive"))
    )
    (net (code "111") (name "Net-(USB1-CC1)") (class "Default")
      (node (ref "R2") (pin "1") (pinfunction "1_1") (pintype "passive"))
      (node (ref "USB1") (pin "3") (pinfunction "CC1_3") (pintype "passive"))
    )
    (net (code "112") (name "Net-(USB1-CC2)") (class "Default")
      (node (ref "R7") (pin "2") (pinfunction "2_2") (pintype "passive"))
      (node (ref "USB1") (pin "11") (pinfunction "CC2_11") (pintype "passive"))
    )
    (net (code "113") (name "Net-(USB2-CC1)") (class "Default")
      (node (ref "R33") (pin "1") (pinfunction "1_1") (pintype "passive"))
      (node (ref "USB2") (pin "4") (pinfunction "CC1_4") (pintype "passive"))
    )
    (net (code "114") (name "Net-(USB2-CC2)") (class "Default")
      (node (ref "R32") (pin "1") (pinfunction "1_1") (pintype "passive"))
      (node (ref "USB2") (pin "10") (pinfunction "CC2_10") (pintype "passive"))
    )
    (net (code "115") (name "VBUS") (class "Default")
      (node (ref "C3") (pin "1") (pinfunction "1_1") (pintype "passive"))
      (node (ref "C50") (pin "2") (pinfunction "2_2") (pintype "passive"))
      (node (ref "C51") (pin "2") (pinfunction "2_2") (pintype "passive"))
      (node (ref "R34") (pin "2") (pinfunction "2_2") (pintype "passive"))
      (node (ref "U12") (pin "3") (pinfunction "VIN_3") (pintype "passive"))
      (node (ref "U3") (pin "1") (pinfunction "EN_1") (pintype "passive"))
      (node (ref "U3") (pin "8") (pinfunction "VIN_8") (pintype "passive"))
      (node (ref "USB1") (pin "10") (pinfunction "VBUS_10") (pintype "passive"))
      (node (ref "USB1") (pin "15") (pinfunction "VBUS_15") (pintype "passive"))
      (node (ref "USB1") (pin "17") (pinfunction "VBUS_17") (pintype "passive"))
      (node (ref "USB1") (pin "2") (pinfunction "VBUS_2") (pintype "passive"))
      (node (ref "USB1") (pin "7") (pinfunction "VBUS_7") (pintype "passive"))
      (node (ref "USB2") (pin "11") (pinfunction "VBUS_11") (pintype "passive"))
      (node (ref "USB2") (pin "2") (pinfunction "VBUS_2") (pintype "passive"))
    )
    (net (code "116") (name "unconnected-(J1-NC-Pad7)") (class "Default")
      (node (ref "J1") (pin "7") (pinfunction "NC_7") (pintype "passive+no_connect"))
    )
    (net (code "117") (name "unconnected-(U2-AT_EN-Pad3)") (class "Default")
      (node (ref "U2") (pin "3") (pinfunction "AT_EN_3") (pintype "passive+no_connect"))
    )
    (net (code "118") (name "unconnected-(U2-DIS_CON-Pad1)") (class "Default")
      (node (ref "U2") (pin "1") (pinfunction "DIS_CON_1") (pintype "passive+no_connect"))
    )
    (net (code "119") (name "unconnected-(U2-NC-Pad2)") (class "Default")
      (node (ref "U2") (pin "2") (pinfunction "NC_2") (pintype "passive+no_connect"))
    )
    (net (code "120") (name "unconnected-(U2-NC-Pad10)") (class "Default")
      (node (ref "U2") (pin "10") (pinfunction "NC_10") (pintype "passive+no_connect"))
    )
    (net (code "121") (name "unconnected-(U2-NC-Pad11)") (class "Default")
      (node (ref "U2") (pin "11") (pinfunction "NC_11") (pintype "passive+no_connect"))
    )
    (net (code "122") (name "unconnected-(U2-NC-Pad13)") (class "Default")
      (node (ref "U2") (pin "13") (pinfunction "NC_13") (pintype "passive+no_connect"))
    )
    (net (code "123") (name "unconnected-(U3-FB-Pad4)") (class "Default")
      (node (ref "U3") (pin "4") (pinfunction "FB_4") (pintype "passive+no_connect"))
    )
    (net (code "124") (name "unconnected-(U3-PG-Pad6)") (class "Default")
      (node (ref "U3") (pin "6") (pinfunction "PG_6") (pintype "passive+no_connect"))
    )
    (net (code "125") (name "unconnected-(U5-GPIO2DCLK1-Pad9)") (class "Default")
      (node (ref "U5") (pin "9") (pinfunction "GPIO2DCLK1_9") (pintype "passive+no_connect"))
    )
    (net (code "126") (name "unconnected-(U5-GPIO3SDATA1-Pad10)") (class "Default")
      (node (ref "U5") (pin "10") (pinfunction "GPIO3SDATA1_10") (pintype "passive+no_connect"))
    )
    (net (code "127") (name "unconnected-(U5-GPIO4I2S-LROUT3-Pad36)") (class "Default")
      (node (ref "U5") (pin "36") (pinfunction "GPIO4I2S-LROUT3_36") (pintype "passive+no_connect"))
    )
    (net (code "128") (name "unconnected-(U5-GPIO6I2S_SCLK3-Pad11)") (class "Default")
      (node (ref "U5") (pin "11") (pinfunction "GPIO6I2S_SCLK3_11") (pintype "passive+no_connect"))
    )
    (net (code "129") (name "unconnected-(U5-GPIO7I2S_SDATA3-Pad12)") (class "Default")
      (node (ref "U5") (pin "12") (pinfunction "GPIO7I2S_SDATA3_12") (pintype "passive+no_connect"))
    )
    (net (code "130") (name "unconnected-(U5-GPIOI2S_MCLK3-Pad25)") (class "Default")
      (node (ref "U5") (pin "25") (pinfunction "GPIOI2S_MCLK3_25") (pintype "passive+no_connect"))
    )
    (net (code "131") (name "unconnected-(U5-LINE2-Pad48)") (class "Default")
      (node (ref "U5") (pin "48") (pinfunction "LINE2_48") (pintype "passive+no_connect"))
    )
    (net (code "132") (name "unconnected-(U5-MICN-Pad2)") (class "Default")
      (node (ref "U5") (pin "2") (pinfunction "MICN_2") (pintype "passive+no_connect"))
    )
    (net (code "133") (name "unconnected-(U5-MICPLINE1-Pad1)") (class "Default")
      (node (ref "U5") (pin "1") (pinfunction "MICPLINE1_1") (pintype "passive+no_connect"))
    )
    (net (code "134") (name "unconnected-(U5-TX-Pad27)") (class "Default")
      (node (ref "U5") (pin "27") (pinfunction "TX_27") (pintype "passive+no_connect"))
    )
    (net (code "135") (name "unconnected-(U5-VCO-Pad15)") (class "Default")
      (node (ref "U5") (pin "15") (pinfunction "VCO_15") (pintype "passive+no_connect"))
    )
    (net (code "136") (name "unconnected-(U7-PA1-Pad11)") (class "Default")
      (node (ref "U7") (pin "11") (pinfunction "PA1_11") (pintype "passive+no_connect"))
    )
    (net (code "137") (name "unconnected-(U7-PA4-Pad14)") (class "Default")
      (node (ref "U7") (pin "14") (pinfunction "PA4_14") (pintype "passive+no_connect"))
    )
    (net (code "138") (name "unconnected-(U7-PA6-Pad16)") (class "Default")
      (node (ref "U7") (pin "16") (pinfunction "PA6_16") (pintype "passive+no_connect"))
    )
    (net (code "139") (name "unconnected-(U7-PA7-Pad17)") (class "Default")
      (node (ref "U7") (pin "17") (pinfunction "PA7_17") (pintype "passive+no_connect"))
    )
    (net (code "140") (name "unconnected-(U7-PA8-Pad29)") (class "Default")
      (node (ref "U7") (pin "29") (pinfunction "PA8_29") (pintype "passive+no_connect"))
    )
    (net (code "141") (name "unconnected-(U7-PB1-Pad19)") (class "Default")
      (node (ref "U7") (pin "19") (pinfunction "PB1_19") (pintype "passive+no_connect"))
    )
    (net (code "142") (name "unconnected-(U7-PB4-Pad40)") (class "Default")
      (node (ref "U7") (pin "40") (pinfunction "PB4_40") (pintype "passive+no_connect"))
    )
    (net (code "143") (name "unconnected-(U7-PB5-Pad41)") (class "Default")
      (node (ref "U7") (pin "41") (pinfunction "PB5_41") (pintype "passive+no_connect"))
    )
    (net (code "144") (name "unconnected-(U7-PB6-Pad42)") (class "Default")
      (node (ref "U7") (pin "42") (pinfunction "PB6_42") (pintype "passive+no_connect"))
    )
    (net (code "145") (name "unconnected-(U7-PB7-Pad43)") (class "Default")
      (node (ref "U7") (pin "43") (pinfunction "PB7_43") (pintype "passive+no_connect"))
    )
    (net (code "146") (name "unconnected-(U7-PB8-Pad45)") (class "Default")
      (node (ref "U7") (pin "45") (pinfunction "PB8_45") (pintype "passive+no_connect"))
    )
    (net (code "147") (name "unconnected-(U7-PB9-Pad46)") (class "Default")
      (node (ref "U7") (pin "46") (pinfunction "PB9_46") (pintype "passive+no_connect"))
    )
    (net (code "148") (name "unconnected-(U7-PB10-Pad21)") (class "Default")
      (node (ref "U7") (pin "21") (pinfunction "PB10_21") (pintype "passive+no_connect"))
    )
    (net (code "149") (name "unconnected-(U7-PB11-Pad22)") (class "Default")
      (node (ref "U7") (pin "22") (pinfunction "PB11_22") (pintype "passive+no_connect"))
    )
    (net (code "150") (name "unconnected-(U7-PB15-Pad28)") (class "Default")
      (node (ref "U7") (pin "28") (pinfunction "PB15_28") (pintype "passive+no_connect"))
    )
    (net (code "151") (name "unconnected-(U7-PC15-OSC32_OUT-Pad4)") (class "Default")
      (node (ref "U7") (pin "4") (pinfunction "PC15-OSC32_OUT_4") (pintype "passive+no_connect"))
    )
    (net (code "152") (name "unconnected-(U8-CFGEN-Pad23)") (class "Default")
      (node (ref "U8") (pin "23") (pinfunction "CFGEN_23") (pintype "passive+no_connect"))
    )
    (net (code "153") (name "unconnected-(U8-NC-Pad1)") (class "Default")
      (node (ref "U8") (pin "1") (pinfunction "NC_1") (pintype "passive+no_connect"))
    )
    (net (code "154") (name "unconnected-(U8-NC-Pad2)") (class "Default")
      (node (ref "U8") (pin "2") (pinfunction "NC_2") (pintype "passive+no_connect"))
    )
    (net (code "155") (name "unconnected-(U8-NC-Pad12)") (class "Default")
      (node (ref "U8") (pin "12") (pinfunction "NC_12") (pintype "passive+no_connect"))
    )
    (net (code "156") (name "unconnected-(U8-NC-Pad13)") (class "Default")
      (node (ref "U8") (pin "13") (pinfunction "NC_13") (pintype "passive+no_connect"))
    )
    (net (code "157") (name "unconnected-(U8-NC-Pad21)") (class "Default")
      (node (ref "U8") (pin "21") (pinfunction "NC_21") (pintype "passive+no_connect"))
    )
    (net (code "158") (name "unconnected-(U8-NC-Pad24)") (class "Default")
      (node (ref "U8") (pin "24") (pinfunction "NC_24") (pintype "passive+no_connect"))
    )
    (net (code "159") (name "unconnected-(U8-RS485DIR-Pad25)") (class "Default")
      (node (ref "U8") (pin "25") (pinfunction "RS485DIR_25") (pintype "passive+no_connect"))
    )
    (net (code "160") (name "unconnected-(U9-ep-Pad5)") (class "Default")
      (node (ref "U9") (pin "5") (pinfunction "ep_5") (pintype "passive+no_connect"))
    )
    (net (code "161") (name "unconnected-(U10-NC-Pad9)") (class "Default")
      (node (ref "U10") (pin "9") (pinfunction "NC_9") (pintype "passive+no_connect"))
    )
    (net (code "162") (name "unconnected-(U10-TP0-Pad1)") (class "Default")
      (node (ref "U10") (pin "1") (pinfunction "TP0_1") (pintype "passive+no_connect"))
    )
    (net (code "163") (name "unconnected-(U10-TP1-Pad2)") (class "Default")
      (node (ref "U10") (pin "2") (pinfunction "TP1_2") (pintype "passive+no_connect"))
    )
    (net (code "164") (name "unconnected-(USB2-SBU1-Pad9)") (class "Default")
      (node (ref "USB2") (pin "9") (pinfunction "SBU1_9") (pintype "passive+no_connect"))
    )
    (net (code "165") (name "unconnected-(USB2-SBU2-Pad3)") (class "Default")
      (node (ref "USB2") (pin "3") (pinfunction "SBU2_3") (pintype "passive+no_connect"))
    )
  )
)
